# 1_P1_schdoc.net
KiCad netlist of a schematic drawn in Altium Designer
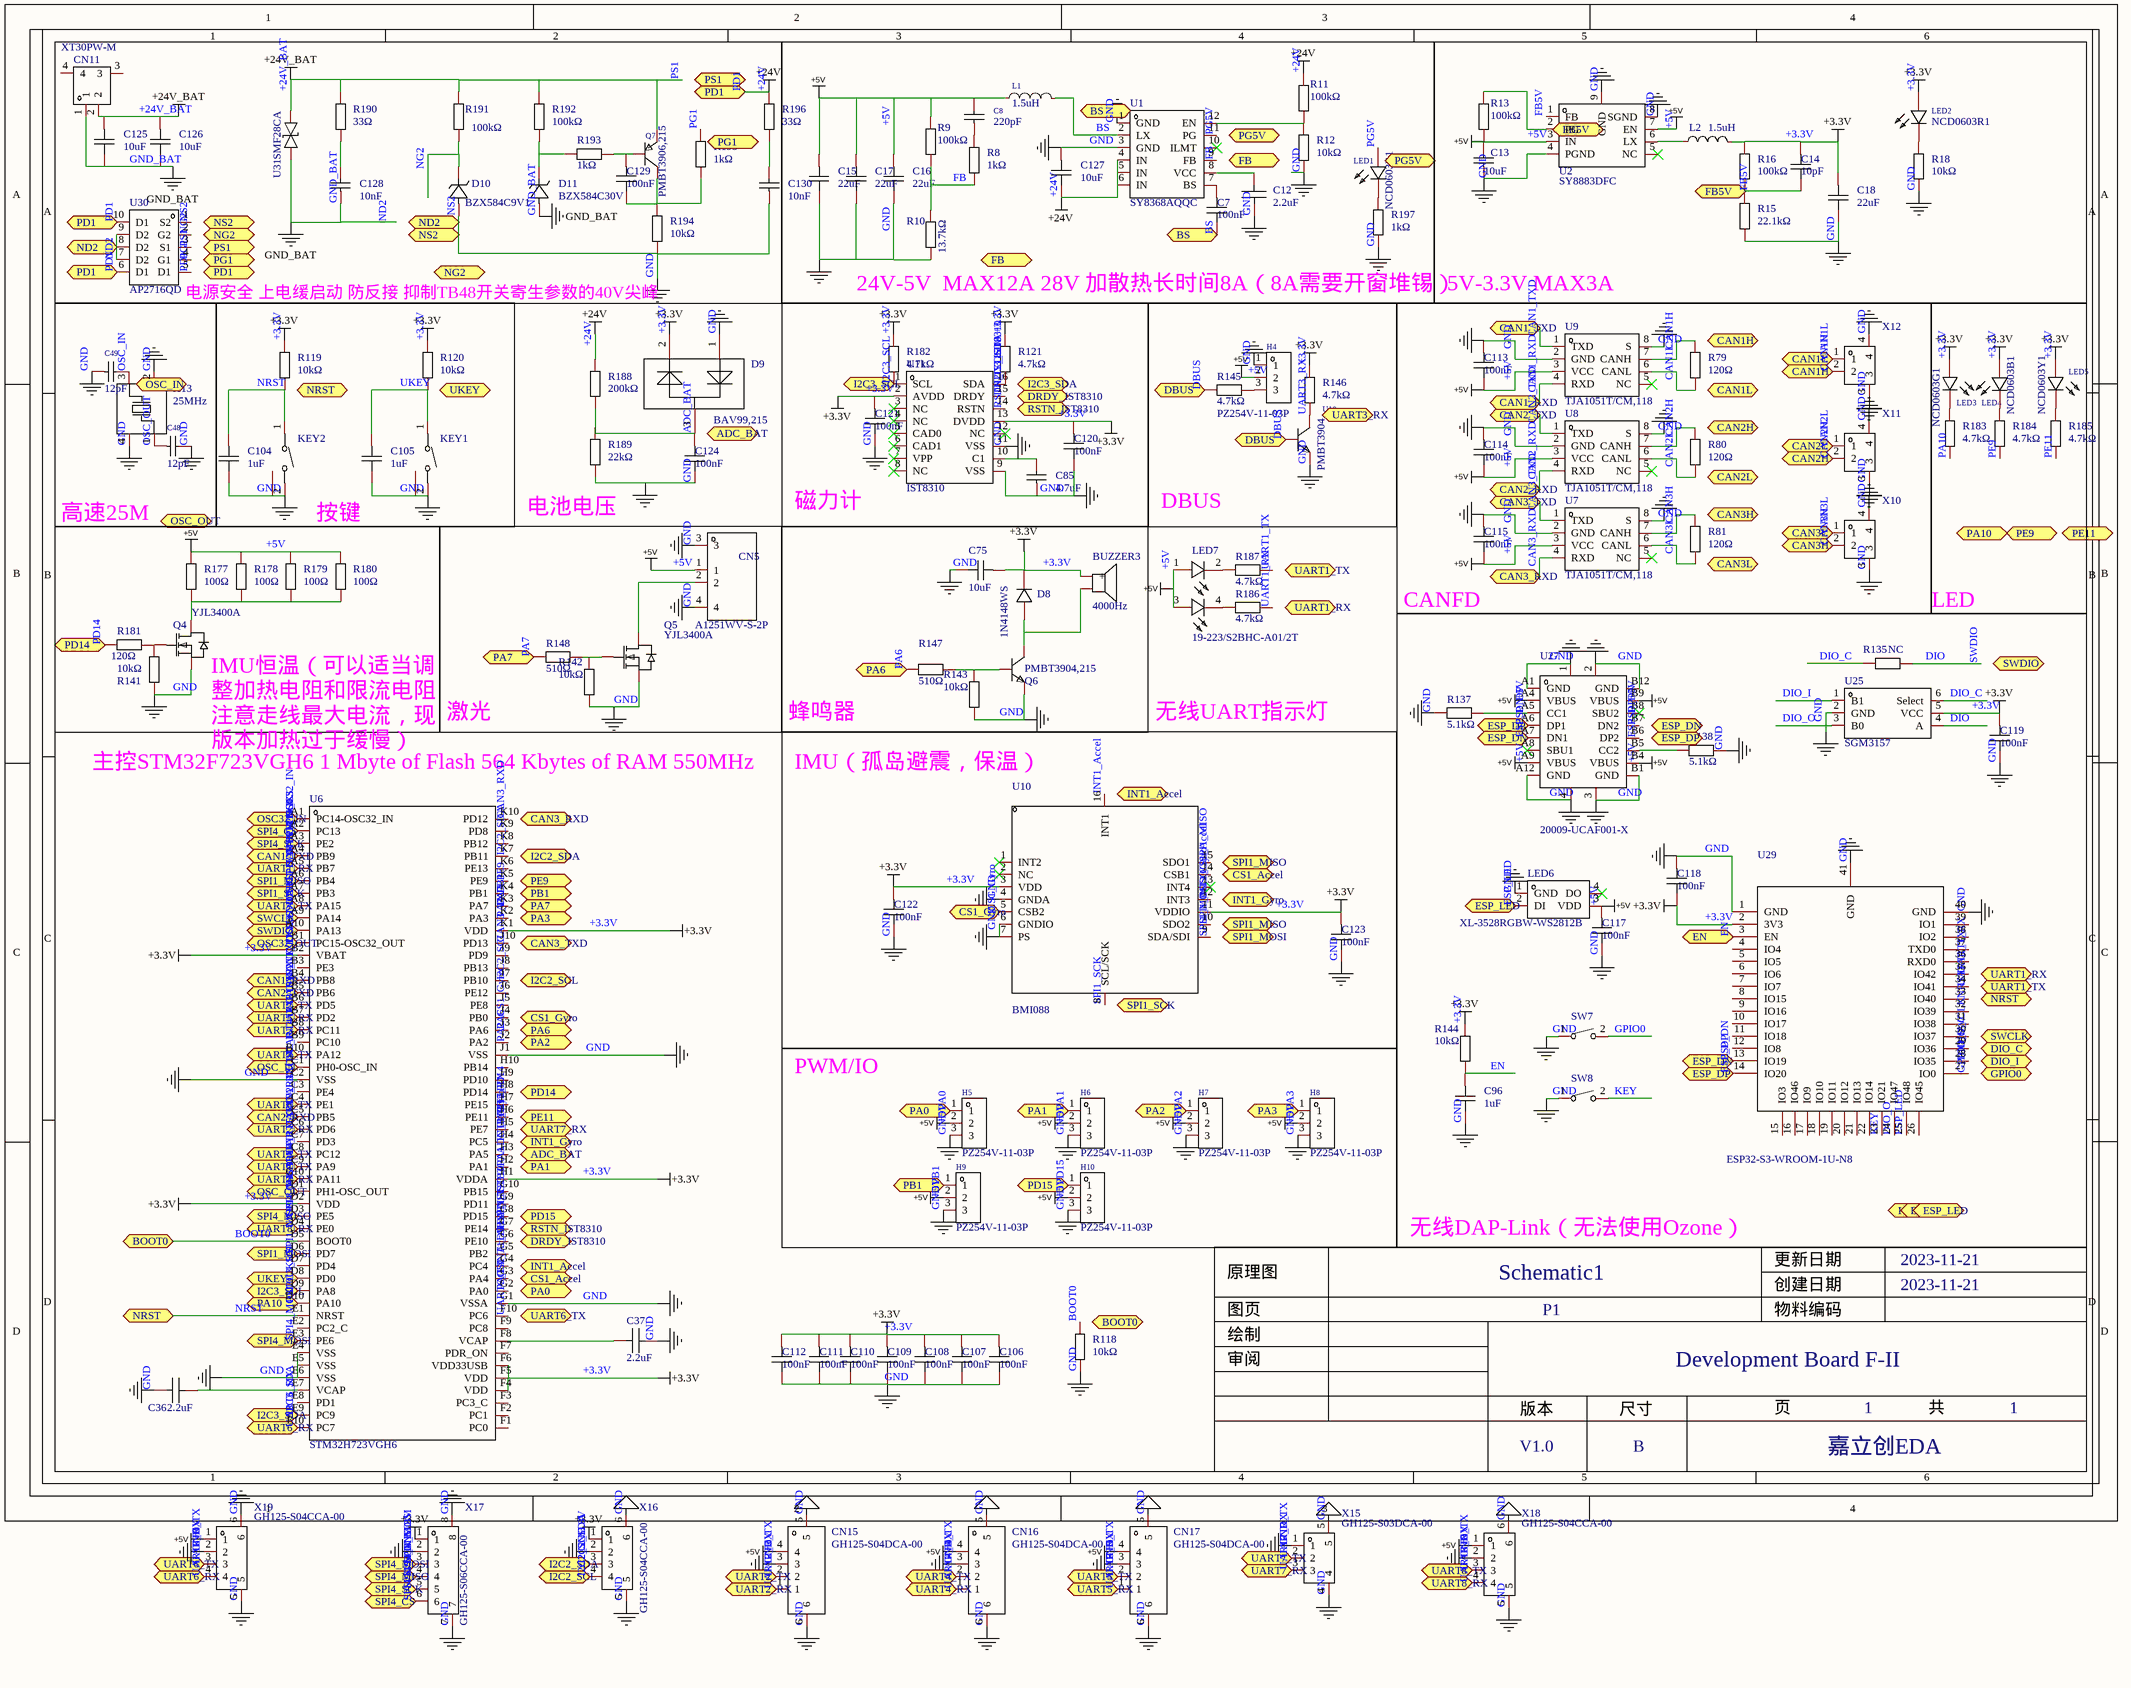
[diagram p0: 1_P1.schdoc.schdoc]

(export (version "E")
  (design (tool "Eeschema 10.0.6"))
  (components
    (comp (ref "BUZZER3")
      (value "4000Hz")
      (description "驱动方式:无源(外部驱动);构造类型:电磁式;额定电压:3V;工作电压:2V~4V;频率:4000Hz;声压(SPL):65dB@3V,10cm;长度:4mm;宽度:4mm;高度:2.5mm;")
      (fields
        (field (name "NAME") "4000Hz")
        (field (name "MANUFACTURER") "FUET(福声科技)")
        (field (name "MANUFACTURER PART") "FUET-4020")
      )
      (libsource (lib "altium-import") (part "root_0_FUET-4020_"))
    )
    (comp (ref "C7")
      (value "100nF")
      (description "容值:100nF;精度:±10%;额定电压:50V;材质(温度系数):X7R;")
      (fields
        (field (name "NAME") "100nF")
        (field (name "MANUFACTURER") "SAMSUNG(三星)")
        (field (name "MANUFACTURER PART") "CL05B104KB54PNC")
      )
      (libsource (lib "altium-import") (part "root_1_CL05B104KB54PNC_"))
    )
    (comp (ref "C8")
      (value "220pF")
      (description "容值:220pF;精度:±10%;额定电压:50V;材质(温度系数):X7R;")
      (fields
        (field (name "NAME") "220pF")
        (field (name "MANUFACTURER") "FH(风华)")
        (field (name "MANUFACTURER PART") "0402B221K500NT")
      )
      (libsource (lib "altium-import") (part "root_1_0402B221K500NT_"))
    )
    (comp (ref "C12")
      (value "2.2uF")
      (description "容值:2.2uF;精度:±20%;额定电压:6.3V;材质(温度系数):X5R;")
      (fields
        (field (name "NAME") "2.2uF")
        (field (name "MANUFACTURER") "SAMSUNG(三星)")
        (field (name "MANUFACTURER PART") "CL05A225MQ5NSNC")
      )
      (libsource (lib "altium-import") (part "root_1_CL05A225MQ5NSNC_"))
    )
    (comp (ref "C13")
      (value "10uF")
      (description "容值:10uF;精度:±20%;额定电压:6.3V;材质(温度系数):X5R;")
      (fields
        (field (name "NAME") "10uF")
        (field (name "MANUFACTURER") "SAMSUNG(三星)")
        (field (name "MANUFACTURER PART") "CL05A106MQ5NUNC")
      )
      (libsource (lib "altium-import") (part "root_1_CL05A106MQ5NUNC_"))
    )
    (comp (ref "C14")
      (value "10pF")
      (description "容值:10pF;精度:±5%;额定电压:50V;材质(温度系数):C0G;")
      (fields
        (field (name "NAME") "10pF")
        (field (name "MANUFACTURER") "SAMSUNG(三星)")
        (field (name "MANUFACTURER PART") "CL05C100JB5NNNC")
      )
      (libsource (lib "altium-import") (part "root_1_CL05C100JB5NNNC_"))
    )
    (comp (ref "C15")
      (value "22uF")
      (description "容值:22uF;精度:±20%;额定电压:6.3V;材质(温度系数):X5R;")
      (fields
        (field (name "NAME") "22uF")
        (field (name "MANUFACTURER") "SAMSUNG(三星)")
        (field (name "MANUFACTURER PART") "CL10A226MQ8NRNC")
      )
      (libsource (lib "altium-import") (part "root_1_CL10A226MQ8NRNC_"))
    )
    (comp (ref "C16")
      (value "22uF")
      (description "容值:22uF;精度:±20%;额定电压:6.3V;材质(温度系数):X5R;")
      (fields
        (field (name "NAME") "22uF")
        (field (name "MANUFACTURER") "SAMSUNG(三星)")
        (field (name "MANUFACTURER PART") "CL10A226MQ8NRNC")
      )
      (libsource (lib "altium-import") (part "root_1_CL10A226MQ8NRNC_"))
    )
    (comp (ref "C17")
      (value "22uF")
      (description "容值:22uF;精度:±20%;额定电压:6.3V;材质(温度系数):X5R;")
      (fields
        (field (name "NAME") "22uF")
        (field (name "MANUFACTURER") "SAMSUNG(三星)")
        (field (name "MANUFACTURER PART") "CL10A226MQ8NRNC")
      )
      (libsource (lib "altium-import") (part "root_1_CL10A226MQ8NRNC_"))
    )
    (comp (ref "C18")
      (value "22uF")
      (description "容值:22uF;精度:±20%;额定电压:6.3V;材质(温度系数):X5R;")
      (fields
        (field (name "NAME") "22uF")
        (field (name "MANUFACTURER") "SAMSUNG(三星)")
        (field (name "MANUFACTURER PART") "CL10A226MQ8NRNC")
      )
      (libsource (lib "altium-import") (part "root_1_CL10A226MQ8NRNC_"))
    )
    (comp (ref "C36")
      (value "2.2uF")
      (description "容值:2.2uF;精度:±20%;额定电压:6.3V;材质(温度系数):X5R;")
      (fields
        (field (name "NAME") "2.2uF")
        (field (name "MANUFACTURER") "SAMSUNG(三星)")
        (field (name "MANUFACTURER PART") "CL05A225MQ5NSNC")
      )
      (libsource (lib "altium-import") (part "root_0_CL05A225MQ5NSNC_"))
    )
    (comp (ref "C37")
      (value "2.2uF")
      (description "容值:2.2uF;精度:±20%;额定电压:6.3V;材质(温度系数):X5R;")
      (fields
        (field (name "NAME") "2.2uF")
        (field (name "MANUFACTURER") "SAMSUNG(三星)")
        (field (name "MANUFACTURER PART") "CL05A225MQ5NSNC")
      )
      (libsource (lib "altium-import") (part "root_0_CL05A225MQ5NSNC_"))
    )
    (comp (ref "C48")
      (value "12pF")
      (description "容值:12pF;精度:±5%;额定电压:50V;材质(温度系数):C0G;")
      (fields
        (field (name "NAME") "12pF")
        (field (name "MANUFACTURER") "FH(风华)")
        (field (name "MANUFACTURER PART") "0402CG120J500NT")
      )
      (libsource (lib "altium-import") (part "root_0_0402CG120J500NT_"))
    )
    (comp (ref "C49")
      (value "12pF")
      (description "容值:12pF;精度:±5%;额定电压:50V;材质(温度系数):C0G;")
      (fields
        (field (name "NAME") "12pF")
        (field (name "MANUFACTURER") "FH(风华)")
        (field (name "MANUFACTURER PART") "0402CG120J500NT")
      )
      (libsource (lib "altium-import") (part "root_0_0402CG120J500NT_"))
    )
    (comp (ref "C75")
      (value "10uF")
      (description "容值:10uF;精度:±20%;额定电压:25V;材质(温度系数):X5R;")
      (fields
        (field (name "NAME") "10uF")
        (field (name "MANUFACTURER") "SAMSUNG(三星)")
        (field (name "MANUFACTURER PART") "CL10A106MA8NRNC")
      )
      (libsource (lib "altium-import") (part "root_0_CL10A106MA8NRNC_"))
    )
    (comp (ref "C85")
      (value "4.7uF")
      (description "容值:4.7uF;精度:±20%;额定电压:10V;材质(温度系数):X5R;")
      (fields
        (field (name "NAME") "4.7uF")
        (field (name "MANUFACTURER") "SAMSUNG(三星)")
        (field (name "MANUFACTURER PART") "CL05A475MP5NRNC")
      )
      (libsource (lib "altium-import") (part "root_1_CL05A475MP5NRNC_"))
    )
    (comp (ref "C96")
      (value "1uF")
      (description "容值:1uF;精度:±10%;额定电压:25V;材质(温度系数):X5R;")
      (fields
        (field (name "NAME") "1uF")
        (field (name "MANUFACTURER") "SAMSUNG(三星)")
        (field (name "MANUFACTURER PART") "CL05A105KA5NQNC")
      )
      (libsource (lib "altium-import") (part "root_1_CL05A105KA5NQNC_"))
    )
    (comp (ref "C104")
      (value "1uF")
      (description "容值:1uF;精度:±10%;额定电压:25V;材质(温度系数):X5R;")
      (fields
        (field (name "NAME") "1uF")
        (field (name "MANUFACTURER") "SAMSUNG(三星)")
        (field (name "MANUFACTURER PART") "CL05A105KA5NQNC")
      )
      (libsource (lib "altium-import") (part "root_1_CL05A105KA5NQNC_"))
    )
    (comp (ref "C105")
      (value "1uF")
      (description "容值:1uF;精度:±10%;额定电压:25V;材质(温度系数):X5R;")
      (fields
        (field (name "NAME") "1uF")
        (field (name "MANUFACTURER") "SAMSUNG(三星)")
        (field (name "MANUFACTURER PART") "CL05A105KA5NQNC")
      )
      (libsource (lib "altium-import") (part "root_1_CL05A105KA5NQNC_"))
    )
    (comp (ref "C106")
      (value "100nF")
      (description "容值:100nF;精度:±10%;额定电压:50V;材质(温度系数):X7R;")
      (fields
        (field (name "NAME") "100nF")
        (field (name "MANUFACTURER") "SAMSUNG(三星)")
        (field (name "MANUFACTURER PART") "CL05B104KB54PNC")
      )
      (libsource (lib "altium-import") (part "root_1_CL05B104KB54PNC_"))
    )
    (comp (ref "C107")
      (value "100nF")
      (description "容值:100nF;精度:±10%;额定电压:50V;材质(温度系数):X7R;")
      (fields
        (field (name "NAME") "100nF")
        (field (name "MANUFACTURER") "SAMSUNG(三星)")
        (field (name "MANUFACTURER PART") "CL05B104KB54PNC")
      )
      (libsource (lib "altium-import") (part "root_1_CL05B104KB54PNC_"))
    )
    (comp (ref "C108")
      (value "100nF")
      (description "容值:100nF;精度:±10%;额定电压:50V;材质(温度系数):X7R;")
      (fields
        (field (name "NAME") "100nF")
        (field (name "MANUFACTURER") "SAMSUNG(三星)")
        (field (name "MANUFACTURER PART") "CL05B104KB54PNC")
      )
      (libsource (lib "altium-import") (part "root_1_CL05B104KB54PNC_"))
    )
    (comp (ref "C109")
      (value "100nF")
      (description "容值:100nF;精度:±10%;额定电压:50V;材质(温度系数):X7R;")
      (fields
        (field (name "NAME") "100nF")
        (field (name "MANUFACTURER") "SAMSUNG(三星)")
        (field (name "MANUFACTURER PART") "CL05B104KB54PNC")
      )
      (libsource (lib "altium-import") (part "root_1_CL05B104KB54PNC_"))
    )
    (comp (ref "C110")
      (value "100nF")
      (description "容值:100nF;精度:±10%;额定电压:50V;材质(温度系数):X7R;")
      (fields
        (field (name "NAME") "100nF")
        (field (name "MANUFACTURER") "SAMSUNG(三星)")
        (field (name "MANUFACTURER PART") "CL05B104KB54PNC")
      )
      (libsource (lib "altium-import") (part "root_1_CL05B104KB54PNC_"))
    )
    (comp (ref "C111")
      (value "100nF")
      (description "容值:100nF;精度:±10%;额定电压:50V;材质(温度系数):X7R;")
      (fields
        (field (name "NAME") "100nF")
        (field (name "MANUFACTURER") "SAMSUNG(三星)")
        (field (name "MANUFACTURER PART") "CL05B104KB54PNC")
      )
      (libsource (lib "altium-import") (part "root_1_CL05B104KB54PNC_"))
    )
    (comp (ref "C112")
      (value "100nF")
      (description "容值:100nF;精度:±10%;额定电压:50V;材质(温度系数):X7R;")
      (fields
        (field (name "NAME") "100nF")
        (field (name "MANUFACTURER") "SAMSUNG(三星)")
        (field (name "MANUFACTURER PART") "CL05B104KB54PNC")
      )
      (libsource (lib "altium-import") (part "root_1_CL05B104KB54PNC_"))
    )
    (comp (ref "C113")
      (value "100nF")
      (description "容值:100nF;精度:±10%;额定电压:50V;材质(温度系数):X7R;")
      (fields
        (field (name "NAME") "100nF")
        (field (name "MANUFACTURER") "SAMSUNG(三星)")
        (field (name "MANUFACTURER PART") "CL05B104KB54PNC")
      )
      (libsource (lib "altium-import") (part "root_1_CL05B104KB54PNC_"))
    )
    (comp (ref "C114")
      (value "100nF")
      (description "容值:100nF;精度:±10%;额定电压:50V;材质(温度系数):X7R;")
      (fields
        (field (name "NAME") "100nF")
        (field (name "MANUFACTURER") "SAMSUNG(三星)")
        (field (name "MANUFACTURER PART") "CL05B104KB54PNC")
      )
      (libsource (lib "altium-import") (part "root_1_CL05B104KB54PNC_"))
    )
    (comp (ref "C115")
      (value "100nF")
      (description "容值:100nF;精度:±10%;额定电压:50V;材质(温度系数):X7R;")
      (fields
        (field (name "NAME") "100nF")
        (field (name "MANUFACTURER") "SAMSUNG(三星)")
        (field (name "MANUFACTURER PART") "CL05B104KB54PNC")
      )
      (libsource (lib "altium-import") (part "root_1_CL05B104KB54PNC_"))
    )
    (comp (ref "C117")
      (value "100nF")
      (description "容值:100nF;精度:±10%;额定电压:50V;材质(温度系数):X7R;")
      (fields
        (field (name "NAME") "100nF")
        (field (name "MANUFACTURER") "SAMSUNG(三星)")
        (field (name "MANUFACTURER PART") "CL05B104KB54PNC")
      )
      (libsource (lib "altium-import") (part "root_1_CL05B104KB54PNC_"))
    )
    (comp (ref "C118")
      (value "100nF")
      (description "容值:100nF;精度:±10%;额定电压:50V;材质(温度系数):X7R;")
      (fields
        (field (name "NAME") "100nF")
        (field (name "MANUFACTURER") "SAMSUNG(三星)")
        (field (name "MANUFACTURER PART") "CL05B104KB54PNC")
      )
      (libsource (lib "altium-import") (part "root_1_CL05B104KB54PNC_"))
    )
    (comp (ref "C119")
      (value "100nF")
      (description "容值:100nF;精度:±10%;额定电压:50V;材质(温度系数):X7R;")
      (fields
        (field (name "NAME") "100nF")
        (field (name "MANUFACTURER") "SAMSUNG(三星)")
        (field (name "MANUFACTURER PART") "CL05B104KB54PNC")
      )
      (libsource (lib "altium-import") (part "root_1_CL05B104KB54PNC_"))
    )
    (comp (ref "C120")
      (value "100nF")
      (description "容值:100nF;精度:±10%;额定电压:50V;材质(温度系数):X7R;")
      (fields
        (field (name "NAME") "100nF")
        (field (name "MANUFACTURER") "SAMSUNG(三星)")
        (field (name "MANUFACTURER PART") "CL05B104KB54PNC")
      )
      (libsource (lib "altium-import") (part "root_1_CL05B104KB54PNC_"))
    )
    (comp (ref "C121")
      (value "100nF")
      (description "容值:100nF;精度:±10%;额定电压:50V;材质(温度系数):X7R;")
      (fields
        (field (name "NAME") "100nF")
        (field (name "MANUFACTURER") "SAMSUNG(三星)")
        (field (name "MANUFACTURER PART") "CL05B104KB54PNC")
      )
      (libsource (lib "altium-import") (part "root_1_CL05B104KB54PNC_"))
    )
    (comp (ref "C122")
      (value "100nF")
      (description "容值:100nF;精度:±10%;额定电压:50V;材质(温度系数):X7R;")
      (fields
        (field (name "NAME") "100nF")
        (field (name "MANUFACTURER") "SAMSUNG(三星)")
        (field (name "MANUFACTURER PART") "CL05B104KB54PNC")
      )
      (libsource (lib "altium-import") (part "root_1_CL05B104KB54PNC_"))
    )
    (comp (ref "C123")
      (value "100nF")
      (description "容值:100nF;精度:±10%;额定电压:50V;材质(温度系数):X7R;")
      (fields
        (field (name "NAME") "100nF")
        (field (name "MANUFACTURER") "SAMSUNG(三星)")
        (field (name "MANUFACTURER PART") "CL05B104KB54PNC")
      )
      (libsource (lib "altium-import") (part "root_1_CL05B104KB54PNC_"))
    )
    (comp (ref "C124")
      (value "100nF")
      (description "容值:100nF;精度:±10%;额定电压:50V;材质(温度系数):X7R;")
      (fields
        (field (name "NAME") "100nF")
        (field (name "MANUFACTURER") "SAMSUNG(三星)")
        (field (name "MANUFACTURER PART") "CL05B104KB54PNC")
      )
      (libsource (lib "altium-import") (part "root_1_CL05B104KB54PNC_"))
    )
    (comp (ref "C125")
      (value "10uF")
      (description "容值:10uF;精度:±10%;额定电压:50V;材质(温度系数):X5R;")
      (fields
        (field (name "NAME") "10uF")
        (field (name "MANUFACTURER") "muRata(村田)")
        (field (name "MANUFACTURER PART") "GRM21BR61H106KE43L")
      )
      (libsource (lib "altium-import") (part "root_1_GRM21BR61H106KE43L_"))
    )
    (comp (ref "C126")
      (value "10uF")
      (description "容值:10uF;精度:±10%;额定电压:50V;材质(温度系数):X5R;")
      (fields
        (field (name "NAME") "10uF")
        (field (name "MANUFACTURER") "muRata(村田)")
        (field (name "MANUFACTURER PART") "GRM21BR61H106KE43L")
      )
      (libsource (lib "altium-import") (part "root_1_GRM21BR61H106KE43L_"))
    )
    (comp (ref "C127")
      (value "10uF")
      (description "容值:10uF;精度:±10%;额定电压:50V;材质(温度系数):X5R;")
      (fields
        (field (name "NAME") "10uF")
        (field (name "MANUFACTURER") "muRata(村田)")
        (field (name "MANUFACTURER PART") "GRM21BR61H106KE43L")
      )
      (libsource (lib "altium-import") (part "root_1_GRM21BR61H106KE43L_"))
    )
    (comp (ref "C128")
      (value "10nF")
      (description "容值:10nF;精度:±10%;额定电压:50V;材质(温度系数):X7R;")
      (fields
        (field (name "NAME") "10nF")
        (field (name "MANUFACTURER") "SAMSUNG(三星)")
        (field (name "MANUFACTURER PART") "CL05B103KB5NNNC")
      )
      (libsource (lib "altium-import") (part "root_1_CL05B103KB5NNNC_"))
    )
    (comp (ref "C129")
      (value "100nF")
      (description "容值:100nF;精度:±10%;额定电压:50V;材质(温度系数):X7R;")
      (fields
        (field (name "NAME") "100nF")
        (field (name "MANUFACTURER") "SAMSUNG(三星)")
        (field (name "MANUFACTURER PART") "CL05B104KB54PNC")
      )
      (libsource (lib "altium-import") (part "root_1_CL05B104KB54PNC_"))
    )
    (comp (ref "C130")
      (value "10nF")
      (description "容值:10nF;精度:±10%;额定电压:50V;材质(温度系数):X7R;")
      (fields
        (field (name "NAME") "10nF")
        (field (name "MANUFACTURER") "SAMSUNG(三星)")
        (field (name "MANUFACTURER PART") "CL05B103KB5NNNC")
      )
      (libsource (lib "altium-import") (part "root_1_CL05B103KB5NNNC_"))
    )
    (comp (ref "CN5")
      (value "A1251WV-S-2P")
      (description "参考系列:-;间距:1.25mm;插针结构:1x2P;排数:1;每排PIN数:2;行距:-;安装方式:-;触头材质:磷青铜;")
      (fields (field (name "NAME") "A1251WV-S-2P") (field (name "MANUFACTURER") "CJT(长江连接器)"))
      (libsource (lib "altium-import") (part "root_0_A1251WV-S-2P_"))
    )
    (comp (ref "CN11")
      (value "XT30PW-M")
      (description "Socket,DCsupply,XT30,male,PIN:2")
      (fields (field (name "NAME") "XT30PW-M") (field (name "MANUFACTURER") "AMASS(艾迈斯)"))
      (libsource (lib "altium-import") (part "root_1_XT30PW-M_"))
    )
    (comp (ref "CN15")
      (value "GH125-S04DCA-00")
      (description "参考系列:-;间距:1.25mm;插针结构:1x4P;排数:1;每排PIN数:4;行距:-;公母:公型插针;安装方式:卧贴;额定电流:1A;工作温度范围:-25℃~+85℃;")
      (fields (field (name "NAME") "GH125-S04DCA-00") (field (name "MANUFACTURER") "JS(钜硕电子)"))
      (libsource (lib "altium-import") (part "root_1_GH125-S04DCA-00_"))
    )
    (comp (ref "CN16")
      (value "GH125-S04DCA-00")
      (description "参考系列:-;间距:1.25mm;插针结构:1x4P;排数:1;每排PIN数:4;行距:-;公母:公型插针;安装方式:卧贴;额定电流:1A;工作温度范围:-25℃~+85℃;")
      (fields (field (name "NAME") "GH125-S04DCA-00") (field (name "MANUFACTURER") "JS(钜硕电子)"))
      (libsource (lib "altium-import") (part "root_1_GH125-S04DCA-00_"))
    )
    (comp (ref "CN17")
      (value "GH125-S04DCA-00")
      (description "参考系列:-;间距:1.25mm;插针结构:1x4P;排数:1;每排PIN数:4;行距:-;公母:公型插针;安装方式:卧贴;额定电流:1A;工作温度范围:-25℃~+85℃;")
      (fields (field (name "NAME") "GH125-S04DCA-00") (field (name "MANUFACTURER") "JS(钜硕电子)"))
      (libsource (lib "altium-import") (part "root_1_GH125-S04DCA-00_"))
    )
    (comp (ref "D8")
      (value "1N4148WS")
      (fields (field (name "NAME") "1N4148WS") (field (name "MANUFACTURER") "CJ(江苏长电/长晶)"))
      (libsource (lib "altium-import") (part "root_3_1N4148WS_C2128_"))
    )
    (comp (ref "D9")
      (value "BAV99,215")
      (description "二极管配置:1对串联式;功率:250mW;直流反向耐压(Vr):100V;平均整流电流(Io):215mA;正向压降(Vf):1.25V@150mA;反向恢复时间(trr):4ns;")
      (fields (field (name "NAME") "BAV99,215") (field (name "MANUFACTURER") "Nexperia(安世)"))
      (libsource (lib "altium-import") (part "root_2_BAV99,215_"))
    )
    (comp (ref "D10")
      (value "BZX584C9V1")
      (description "二极管配置:独立式;稳压值(标称值):9.1V;稳压值(范围):8.5V~9.6V;精度:-;功率:200mW;反向电流(Ir):200nA@7V;阻抗(Zzt):15Ω;")
      (fields (field (name "NAME") "BZX584C9V1") (field (name "MANUFACTURER") "YANGJIE(扬杰)"))
      (libsource (lib "altium-import") (part "root_3_BZX584C9V1_"))
    )
    (comp (ref "D11")
      (value "BZX584C30V")
      (description "二极管配置:独立式;稳压值(标称值):30V;稳压值(范围):28V~32V;精度:-;功率:200mW;反向电流(Ir):50nA@21V;阻抗(Zzt):80Ω;")
      (fields (field (name "NAME") "BZX584C30V") (field (name "MANUFACTURER") "YANGJIE(扬杰)"))
      (libsource (lib "altium-import") (part "root_3_BZX584C30V_"))
    )
    (comp (ref "H4")
      (value "PZ254V-11-03P")
      (fields (field (name "NAME") "PZ254V-11-03P") (field (name "MANUFACTURER") "XFCN(兴飞)"))
      (libsource (lib "altium-import") (part "root_0_PZ254V-11-03P_"))
    )
    (comp (ref "H5")
      (value "PZ254V-11-03P")
      (fields (field (name "NAME") "PZ254V-11-03P") (field (name "MANUFACTURER") "XFCN(兴飞)"))
      (libsource (lib "altium-import") (part "root_0_PZ254V-11-03P_"))
    )
    (comp (ref "H6")
      (value "PZ254V-11-03P")
      (fields (field (name "NAME") "PZ254V-11-03P") (field (name "MANUFACTURER") "XFCN(兴飞)"))
      (libsource (lib "altium-import") (part "root_0_PZ254V-11-03P_"))
    )
    (comp (ref "H7")
      (value "PZ254V-11-03P")
      (fields (field (name "NAME") "PZ254V-11-03P") (field (name "MANUFACTURER") "XFCN(兴飞)"))
      (libsource (lib "altium-import") (part "root_0_PZ254V-11-03P_"))
    )
    (comp (ref "H8")
      (value "PZ254V-11-03P")
      (fields (field (name "NAME") "PZ254V-11-03P") (field (name "MANUFACTURER") "XFCN(兴飞)"))
      (libsource (lib "altium-import") (part "root_0_PZ254V-11-03P_"))
    )
    (comp (ref "H9")
      (value "PZ254V-11-03P")
      (fields (field (name "NAME") "PZ254V-11-03P") (field (name "MANUFACTURER") "XFCN(兴飞)"))
      (libsource (lib "altium-import") (part "root_0_PZ254V-11-03P_"))
    )
    (comp (ref "H10")
      (value "PZ254V-11-03P")
      (fields (field (name "NAME") "PZ254V-11-03P") (field (name "MANUFACTURER") "XFCN(兴飞)"))
      (libsource (lib "altium-import") (part "root_0_PZ254V-11-03P_"))
    )
    (comp (ref "KEY1")
      (value "1TS003B-2500-3500A-CT")
      (fields (field (name "MANUFACTURER") "HYP(鸿源精密)"))
      (libsource (lib "altium-import") (part "root_3_1TS003B-2500-3500A-CT_"))
    )
    (comp (ref "KEY2")
      (value "1TS003B-2500-3500A-CT")
      (fields (field (name "MANUFACTURER") "HYP(鸿源精密)"))
      (libsource (lib "altium-import") (part "root_3_1TS003B-2500-3500A-CT_"))
    )
    (comp (ref "L1")
      (value "1.5uH")
      (description "类型:一体成型电感;电感值:1.5uH;精度:±20%;额定电流:9A;饱和电流(Isat):15A;")
      (fields
        (field (name "NAME") "1.5uH")
        (field (name "MANUFACTURER") "cjiang(长江微电)")
        (field (name "MANUFACTURER PART") "FXL0624-1R5-M")
      )
      (libsource (lib "altium-import") (part "root_0_FXL0624-1R5-M_"))
    )
    (comp (ref "L2")
      (value "1.5uH")
      (description "电感值:1.5uH;精度:±20%;额定电流:-;饱和电流(Isat):-;")
      (fields
        (field (name "NAME") "1.5uH")
        (field (name "MANUFACTURER") "muRata(村田)")
        (field (name "MANUFACTURER PART") "DFE201610E-1R5M=P2")
      )
      (libsource (lib "altium-import") (part "root_0_DFE201610E-1R5M=P2_"))
    )
    (comp (ref "LED1")
      (value "NCD0603R1")
      (description "发光颜色:红灯;")
      (fields (field (name "NAME") "NCD0603R1") (field (name "MANUFACTURER") "国星光电"))
      (libsource (lib "altium-import") (part "root_1_NCD0603R1_C84263_"))
    )
    (comp (ref "LED2")
      (value "NCD0603R1")
      (description "发光颜色:红灯;")
      (fields (field (name "NAME") "NCD0603R1") (field (name "MANUFACTURER") "国星光电"))
      (libsource (lib "altium-import") (part "root_1_NCD0603R1_C84263_"))
    )
    (comp (ref "LED3")
      (value "NCD0603G1")
      (description "发光颜色:翠绿;")
      (fields (field (name "NAME") "NCD0603G1") (field (name "MANUFACTURER") "国星光电"))
      (libsource (lib "altium-import") (part "root_3_NCD0603G1_"))
    )
    (comp (ref "LED4")
      (value "NCD0603B1")
      (description "发光颜色:蓝灯;")
      (fields (field (name "NAME") "NCD0603B1") (field (name "MANUFACTURER") "国星光电"))
      (libsource (lib "altium-import") (part "root_1_NCD0603B1_"))
    )
    (comp (ref "LED5")
      (value "NCD0603Y1")
      (description "发光颜色:黄灯;")
      (fields (field (name "NAME") "NCD0603Y1") (field (name "MANUFACTURER") "国星光电"))
      (libsource (lib "altium-import") (part "root_3_NCD0603Y1_"))
    )
    (comp (ref "LED6")
      (value "XL-3528RGBW-WS2812B")
      (description "发光颜色:RGB三色;二极管配置:-;主波长:618nm~623nm；520nm~525nm；467nm~472nm;功率:50mW；50mW；45mW;安装方式:正贴;")
      (fields (field (name "NAME") "XL-3528RGBW-WS2812B") (field (name "MANUFACTURER") "XINGLIGHT(成兴光)"))
      (libsource (lib "altium-import") (part "root_0_XL-3528RGBW-WS2812B_"))
    )
    (comp (ref "LED7")
      (value "19-223/S2BHC-A01/2T")
      (description "发光颜色:橙灯,蓝灯;二极管配置:-;透镜颜色:无色透明;主波长:470nm；605nm;色温:-;功率:60mW；75mW;发光角度:120°;安装方式:-;工作温度:-40℃~+85℃;")
      (fields (field (name "NAME") "19-223/S2BHC-A01/2T") (field (name "MANUFACTURER") "EVERLIGHT(亿光)"))
      (libsource (lib "altium-import") (part "root_2_19-223/S2BHC-A01/2T_"))
    )
    (comp (ref "Q4")
      (value "YJL3400A")
      (description "类型:N沟道;漏源电压(Vdss):30V;连续漏极电流(Id):5.6A;功率(Pd):1.2W;导通电阻(RDS(on)@Vgs,Id):27mΩ@10V,5.6A;")
      (fields (field (name "NAME") "YJL3400A") (field (name "MANUFACTURER") "YANGJIE(扬杰)"))
      (libsource (lib "altium-import") (part "root_0_YJL3400A_"))
    )
    (comp (ref "Q5")
      (value "YJL3400A")
      (description "类型:N沟道;漏源电压(Vdss):30V;连续漏极电流(Id):5.6A;功率(Pd):1.2W;导通电阻(RDS(on)@Vgs,Id):27mΩ@10V,5.6A;")
      (fields (field (name "NAME") "YJL3400A") (field (name "MANUFACTURER") "YANGJIE(扬杰)"))
      (libsource (lib "altium-import") (part "root_0_YJL3400A_"))
    )
    (comp (ref "Q6")
      (value "PMBT3904,215")
      (description "晶体管类型:NPN;集射极击穿电压(Vceo):40V;集电极电流(Ic):200mA;功率(Pd):250mW;直流电流增益(hFE@Ic,Vce):100@10mA,1V;")
      (fields (field (name "NAME") "PMBT3904,215") (field (name "MANUFACTURER") "Nexperia(安世)"))
      (libsource (lib "altium-import") (part "root_0_PMBT3904,215_"))
    )
    (comp (ref "Q7")
      (value "PMBT3906,215")
      (description "晶体管类型:PNP;集射极击穿电压(Vceo):40V;集电极电流(Ic):200mA;功率(Pd):250mW;直流电流增益(hFE@Ic,Vce):100@10mA,1V;")
      (fields (field (name "NAME") "PMBT3906,215") (field (name "MANUFACTURER") "Nexperia(安世)"))
      (libsource (lib "altium-import") (part "root_2_mirrored_PMBT3906,215_"))
    )
    (comp (ref "R8")
      (value "1kΩ")
      (description "电阻类型:厚膜电阻;阻值:1kΩ;精度:±1%;功率:62.5mW;")
      (fields
        (field (name "NAME") "1kΩ")
        (field (name "MANUFACTURER") "UNI-ROYAL(厚声)")
        (field (name "MANUFACTURER PART") "0402WGF1001TCE")
      )
      (libsource (lib "altium-import") (part "root_1_0402WGF1001TCE_"))
    )
    (comp (ref "R9")
      (value "100kΩ")
      (description "电阻类型:厚膜电阻;阻值:100kΩ;精度:±1%;功率:62.5mW;")
      (fields
        (field (name "NAME") "100kΩ")
        (field (name "MANUFACTURER") "UNI-ROYAL(厚声)")
        (field (name "MANUFACTURER PART") "0402WGF1003TCE")
      )
      (libsource (lib "altium-import") (part "root_1_0402WGF1003TCE_"))
    )
    (comp (ref "R10")
      (value "13.7kΩ")
      (description "电阻类型:厚膜电阻;阻值:13.7kΩ;精度:±1%;功率:62.5mW;温度系数:±100ppm/℃;")
      (fields
        (field (name "NAME") "13.7kΩ")
        (field (name "MANUFACTURER") "UNI-ROYAL(厚声)")
        (field (name "MANUFACTURER PART") "0402WGF1372TCE")
      )
      (libsource (lib "altium-import") (part "root_1_0402WGF1372TCE_"))
    )
    (comp (ref "R11")
      (value "100kΩ")
      (description "电阻类型:厚膜电阻;阻值:100kΩ;精度:±1%;功率:62.5mW;")
      (fields
        (field (name "NAME") "100kΩ")
        (field (name "MANUFACTURER") "UNI-ROYAL(厚声)")
        (field (name "MANUFACTURER PART") "0402WGF1003TCE")
      )
      (libsource (lib "altium-import") (part "root_1_0402WGF1003TCE_"))
    )
    (comp (ref "R12")
      (value "10kΩ")
      (description "电阻类型:厚膜电阻;阻值:10kΩ;精度:±1%;功率:62.5mW;温度系数:±100ppm/℃;")
      (fields
        (field (name "NAME") "10kΩ")
        (field (name "MANUFACTURER") "UNI-ROYAL(厚声)")
        (field (name "MANUFACTURER PART") "0402WGF1002TCE")
      )
      (libsource (lib "altium-import") (part "root_1_0402WGF1002TCE_"))
    )
    (comp (ref "R13")
      (value "100kΩ")
      (description "电阻类型:厚膜电阻;阻值:100kΩ;精度:±1%;功率:62.5mW;")
      (fields
        (field (name "NAME") "100kΩ")
        (field (name "MANUFACTURER") "UNI-ROYAL(厚声)")
        (field (name "MANUFACTURER PART") "0402WGF1003TCE")
      )
      (libsource (lib "altium-import") (part "root_1_0402WGF1003TCE_"))
    )
    (comp (ref "R15")
      (value "22.1kΩ")
      (description "电阻类型:厚膜电阻;阻值:22.1kΩ;精度:±1%;功率:62.5mW;")
      (fields
        (field (name "NAME") "22.1kΩ")
        (field (name "MANUFACTURER") "UNI-ROYAL(厚声)")
        (field (name "MANUFACTURER PART") "0402WGF2212TCE")
      )
      (libsource (lib "altium-import") (part "root_1_0402WGF2212TCE_"))
    )
    (comp (ref "R16")
      (value "100kΩ")
      (description "电阻类型:厚膜电阻;阻值:100kΩ;精度:±1%;功率:62.5mW;")
      (fields
        (field (name "NAME") "100kΩ")
        (field (name "MANUFACTURER") "UNI-ROYAL(厚声)")
        (field (name "MANUFACTURER PART") "0402WGF1003TCE")
      )
      (libsource (lib "altium-import") (part "root_3_0402WGF1003TCE_"))
    )
    (comp (ref "R18")
      (value "10kΩ")
      (description "电阻类型:厚膜电阻;阻值:10kΩ;精度:±1%;功率:62.5mW;温度系数:±100ppm/℃;")
      (fields
        (field (name "NAME") "10kΩ")
        (field (name "MANUFACTURER") "UNI-ROYAL(厚声)")
        (field (name "MANUFACTURER PART") "0402WGF1002TCE")
      )
      (libsource (lib "altium-import") (part "root_1_0402WGF1002TCE_"))
    )
    (comp (ref "R79")
      (value "120Ω")
      (description "电阻类型:厚膜电阻;阻值:120Ω;精度:±1%;功率:62.5mW;")
      (fields
        (field (name "NAME") "120Ω")
        (field (name "MANUFACTURER") "UNI-ROYAL(厚声)")
        (field (name "MANUFACTURER PART") "0402WGF1200TCE")
      )
      (libsource (lib "altium-import") (part "root_1_0402WGF1200TCE_"))
    )
    (comp (ref "R80")
      (value "120Ω")
      (description "电阻类型:厚膜电阻;阻值:120Ω;精度:±1%;功率:62.5mW;")
      (fields
        (field (name "NAME") "120Ω")
        (field (name "MANUFACTURER") "UNI-ROYAL(厚声)")
        (field (name "MANUFACTURER PART") "0402WGF1200TCE")
      )
      (libsource (lib "altium-import") (part "root_1_0402WGF1200TCE_"))
    )
    (comp (ref "R81")
      (value "120Ω")
      (description "电阻类型:厚膜电阻;阻值:120Ω;精度:±1%;功率:62.5mW;")
      (fields
        (field (name "NAME") "120Ω")
        (field (name "MANUFACTURER") "UNI-ROYAL(厚声)")
        (field (name "MANUFACTURER PART") "0402WGF1200TCE")
      )
      (libsource (lib "altium-import") (part "root_1_0402WGF1200TCE_"))
    )
    (comp (ref "R118")
      (value "10kΩ")
      (description "电阻类型:厚膜电阻;阻值:10kΩ;精度:±1%;功率:62.5mW;温度系数:±100ppm/℃;")
      (fields
        (field (name "NAME") "10kΩ")
        (field (name "MANUFACTURER") "UNI-ROYAL(厚声)")
        (field (name "MANUFACTURER PART") "0402WGF1002TCE")
      )
      (libsource (lib "altium-import") (part "root_1_0402WGF1002TCE_"))
    )
    (comp (ref "R119")
      (value "10kΩ")
      (description "电阻类型:厚膜电阻;阻值:10kΩ;精度:±1%;功率:62.5mW;温度系数:±100ppm/℃;")
      (fields
        (field (name "NAME") "10kΩ")
        (field (name "MANUFACTURER") "UNI-ROYAL(厚声)")
        (field (name "MANUFACTURER PART") "0402WGF1002TCE")
      )
      (libsource (lib "altium-import") (part "root_1_0402WGF1002TCE_"))
    )
    (comp (ref "R120")
      (value "10kΩ")
      (description "电阻类型:厚膜电阻;阻值:10kΩ;精度:±1%;功率:62.5mW;温度系数:±100ppm/℃;")
      (fields
        (field (name "NAME") "10kΩ")
        (field (name "MANUFACTURER") "UNI-ROYAL(厚声)")
        (field (name "MANUFACTURER PART") "0402WGF1002TCE")
      )
      (libsource (lib "altium-import") (part "root_1_0402WGF1002TCE_"))
    )
    (comp (ref "R121")
      (value "4.7kΩ")
      (description "电阻类型:厚膜电阻;阻值:4.7kΩ;精度:±1%;功率:62.5mW;")
      (fields
        (field (name "NAME") "4.7kΩ")
        (field (name "MANUFACTURER") "UNI-ROYAL(厚声)")
        (field (name "MANUFACTURER PART") "0402WGF4701TCE")
      )
      (libsource (lib "altium-import") (part "root_1_0402WGF4701TCE_"))
    )
    (comp (ref "R135")
      (value "NC")
      (fields (field (name "Comment") "R0402"))
      (libsource (lib "altium-import") (part "root_0_R0402_"))
    )
    (comp (ref "R137")
      (value "5.1kΩ")
      (description "电阻类型:厚膜电阻;阻值:5.1kΩ;精度:±1%;功率:62.5mW;")
      (fields
        (field (name "NAME") "5.1kΩ")
        (field (name "MANUFACTURER") "UNI-ROYAL(厚声)")
        (field (name "MANUFACTURER PART") "0402WGF5101TCE")
      )
      (libsource (lib "altium-import") (part "root_0_0402WGF5101TCE_"))
    )
    (comp (ref "R138")
      (value "5.1kΩ")
      (description "电阻类型:厚膜电阻;阻值:5.1kΩ;精度:±1%;功率:62.5mW;")
      (fields
        (field (name "NAME") "5.1kΩ")
        (field (name "MANUFACTURER") "UNI-ROYAL(厚声)")
        (field (name "MANUFACTURER PART") "0402WGF5101TCE")
      )
      (libsource (lib "altium-import") (part "root_0_0402WGF5101TCE_"))
    )
    (comp (ref "R141")
      (value "10kΩ")
      (description "电阻类型:厚膜电阻;阻值:10kΩ;精度:±1%;功率:62.5mW;")
      (fields
        (field (name "NAME") "10kΩ")
        (field (name "MANUFACTURER") "UNI-ROYAL(厚声)")
        (field (name "MANUFACTURER PART") "0402WGF1002TCE")
      )
      (libsource (lib "altium-import") (part "root_1_0402WGF1002TCE_"))
    )
    (comp (ref "R142")
      (value "10kΩ")
      (description "电阻类型:厚膜电阻;阻值:10kΩ;精度:±1%;功率:62.5mW;")
      (fields
        (field (name "NAME") "10kΩ")
        (field (name "MANUFACTURER") "UNI-ROYAL(厚声)")
        (field (name "MANUFACTURER PART") "0402WGF1002TCE")
      )
      (libsource (lib "altium-import") (part "root_1_0402WGF1002TCE_"))
    )
    (comp (ref "R143")
      (value "10kΩ")
      (description "电阻类型:厚膜电阻;阻值:10kΩ;精度:±1%;功率:62.5mW;")
      (fields
        (field (name "NAME") "10kΩ")
        (field (name "MANUFACTURER") "UNI-ROYAL(厚声)")
        (field (name "MANUFACTURER PART") "0402WGF1002TCE")
      )
      (libsource (lib "altium-import") (part "root_1_0402WGF1002TCE_"))
    )
    (comp (ref "R144")
      (value "10kΩ")
      (description "电阻类型:厚膜电阻;阻值:10kΩ;精度:±1%;功率:62.5mW;")
      (fields
        (field (name "NAME") "10kΩ")
        (field (name "MANUFACTURER") "UNI-ROYAL(厚声)")
        (field (name "MANUFACTURER PART") "0402WGF1002TCE")
      )
      (libsource (lib "altium-import") (part "root_1_0402WGF1002TCE_"))
    )
    (comp (ref "R145")
      (value "4.7kΩ")
      (description "电阻类型:厚膜电阻;阻值:4.7kΩ;精度:±1%;功率:62.5mW;")
      (fields
        (field (name "NAME") "4.7kΩ")
        (field (name "MANUFACTURER") "UNI-ROYAL(厚声)")
        (field (name "MANUFACTURER PART") "0402WGF4701TCE")
      )
      (libsource (lib "altium-import") (part "root_0_0402WGF4701TCE_"))
    )
    (comp (ref "R146")
      (value "4.7kΩ")
      (description "电阻类型:厚膜电阻;阻值:4.7kΩ;精度:±1%;功率:62.5mW;")
      (fields
        (field (name "NAME") "4.7kΩ")
        (field (name "MANUFACTURER") "UNI-ROYAL(厚声)")
        (field (name "MANUFACTURER PART") "0402WGF4701TCE")
      )
      (libsource (lib "altium-import") (part "root_1_0402WGF4701TCE_"))
    )
    (comp (ref "R147")
      (value "510Ω")
      (description "电阻类型:厚膜电阻;阻值:510Ω;精度:±1%;功率:62.5mW;")
      (fields
        (field (name "NAME") "510Ω")
        (field (name "MANUFACTURER") "UNI-ROYAL(厚声)")
        (field (name "MANUFACTURER PART") "0402WGF5100TCE")
      )
      (libsource (lib "altium-import") (part "root_0_0402WGF5100TCE_"))
    )
    (comp (ref "R148")
      (value "510Ω")
      (description "电阻类型:厚膜电阻;阻值:510Ω;精度:±1%;功率:62.5mW;")
      (fields
        (field (name "NAME") "510Ω")
        (field (name "MANUFACTURER") "UNI-ROYAL(厚声)")
        (field (name "MANUFACTURER PART") "0402WGF5100TCE")
      )
      (libsource (lib "altium-import") (part "root_0_0402WGF5100TCE_"))
    )
    (comp (ref "R177")
      (value "100Ω")
      (description "电阻类型:厚膜电阻;阻值:100Ω;精度:±1%;功率:100mW;温度系数:±200ppm/℃;")
      (fields
        (field (name "NAME") "100Ω")
        (field (name "MANUFACTURER") "UNI-ROYAL(厚声)")
        (field (name "MANUFACTURER PART") "0603WAF1000T5E")
      )
      (libsource (lib "altium-import") (part "root_1_0603WAF1000T5E_"))
    )
    (comp (ref "R178")
      (value "100Ω")
      (description "电阻类型:厚膜电阻;阻值:100Ω;精度:±1%;功率:100mW;温度系数:±200ppm/℃;")
      (fields
        (field (name "NAME") "100Ω")
        (field (name "MANUFACTURER") "UNI-ROYAL(厚声)")
        (field (name "MANUFACTURER PART") "0603WAF1000T5E")
      )
      (libsource (lib "altium-import") (part "root_1_0603WAF1000T5E_"))
    )
    (comp (ref "R179")
      (value "100Ω")
      (description "电阻类型:厚膜电阻;阻值:100Ω;精度:±1%;功率:100mW;温度系数:±200ppm/℃;")
      (fields
        (field (name "NAME") "100Ω")
        (field (name "MANUFACTURER") "UNI-ROYAL(厚声)")
        (field (name "MANUFACTURER PART") "0603WAF1000T5E")
      )
      (libsource (lib "altium-import") (part "root_1_0603WAF1000T5E_"))
    )
    (comp (ref "R180")
      (value "100Ω")
      (description "电阻类型:厚膜电阻;阻值:100Ω;精度:±1%;功率:100mW;温度系数:±200ppm/℃;")
      (fields
        (field (name "NAME") "100Ω")
        (field (name "MANUFACTURER") "UNI-ROYAL(厚声)")
        (field (name "MANUFACTURER PART") "0603WAF1000T5E")
      )
      (libsource (lib "altium-import") (part "root_1_0603WAF1000T5E_"))
    )
    (comp (ref "R181")
      (value "120Ω")
      (description "电阻类型:厚膜电阻;阻值:120Ω;精度:±1%;功率:62.5mW;")
      (fields
        (field (name "NAME") "120Ω")
        (field (name "MANUFACTURER") "UNI-ROYAL(厚声)")
        (field (name "MANUFACTURER PART") "0402WGF1200TCE")
      )
      (libsource (lib "altium-import") (part "root_2_0402WGF1200TCE_"))
    )
    (comp (ref "R182")
      (value "4.7kΩ")
      (description "电阻类型:厚膜电阻;阻值:4.7kΩ;精度:±1%;功率:62.5mW;")
      (fields
        (field (name "NAME") "4.7kΩ")
        (field (name "MANUFACTURER") "UNI-ROYAL(厚声)")
        (field (name "MANUFACTURER PART") "0402WGF4701TCE")
      )
      (libsource (lib "altium-import") (part "root_1_0402WGF4701TCE_"))
    )
    (comp (ref "R183")
      (value "4.7kΩ")
      (description "电阻类型:厚膜电阻;阻值:4.7kΩ;精度:±1%;功率:62.5mW;")
      (fields
        (field (name "NAME") "4.7kΩ")
        (field (name "MANUFACTURER") "UNI-ROYAL(厚声)")
        (field (name "MANUFACTURER PART") "0402WGF4701TCE")
      )
      (libsource (lib "altium-import") (part "root_1_0402WGF4701TCE_"))
    )
    (comp (ref "R184")
      (value "4.7kΩ")
      (description "电阻类型:厚膜电阻;阻值:4.7kΩ;精度:±1%;功率:62.5mW;")
      (fields
        (field (name "NAME") "4.7kΩ")
        (field (name "MANUFACTURER") "UNI-ROYAL(厚声)")
        (field (name "MANUFACTURER PART") "0402WGF4701TCE")
      )
      (libsource (lib "altium-import") (part "root_1_0402WGF4701TCE_"))
    )
    (comp (ref "R185")
      (value "4.7kΩ")
      (description "电阻类型:厚膜电阻;阻值:4.7kΩ;精度:±1%;功率:62.5mW;")
      (fields
        (field (name "NAME") "4.7kΩ")
        (field (name "MANUFACTURER") "UNI-ROYAL(厚声)")
        (field (name "MANUFACTURER PART") "0402WGF4701TCE")
      )
      (libsource (lib "altium-import") (part "root_1_0402WGF4701TCE_"))
    )
    (comp (ref "R186")
      (value "4.7kΩ")
      (description "电阻类型:厚膜电阻;阻值:4.7kΩ;精度:±1%;功率:62.5mW;")
      (fields
        (field (name "NAME") "4.7kΩ")
        (field (name "MANUFACTURER") "UNI-ROYAL(厚声)")
        (field (name "MANUFACTURER PART") "0402WGF4701TCE")
      )
      (libsource (lib "altium-import") (part "root_0_0402WGF4701TCE_"))
    )
    (comp (ref "R187")
      (value "4.7kΩ")
      (description "电阻类型:厚膜电阻;阻值:4.7kΩ;精度:±1%;功率:62.5mW;")
      (fields
        (field (name "NAME") "4.7kΩ")
        (field (name "MANUFACTURER") "UNI-ROYAL(厚声)")
        (field (name "MANUFACTURER PART") "0402WGF4701TCE")
      )
      (libsource (lib "altium-import") (part "root_0_0402WGF4701TCE_"))
    )
    (comp (ref "R188")
      (value "200kΩ")
      (description "电阻类型:厚膜电阻;阻值:200kΩ;精度:±1%;功率:62.5mW;温度系数:±100ppm/℃;")
      (fields
        (field (name "NAME") "200kΩ")
        (field (name "MANUFACTURER") "UNI-ROYAL(厚声)")
        (field (name "MANUFACTURER PART") "0402WGF2003TCE")
      )
      (libsource (lib "altium-import") (part "root_1_0402WGF2003TCE_"))
    )
    (comp (ref "R189")
      (value "22kΩ")
      (description "电阻类型:厚膜电阻;阻值:22kΩ;精度:±1%;功率:62.5mW;温度系数:±100ppm/℃;")
      (fields
        (field (name "NAME") "22kΩ")
        (field (name "MANUFACTURER") "UNI-ROYAL(厚声)")
        (field (name "MANUFACTURER PART") "0402WGF2202TCE")
      )
      (libsource (lib "altium-import") (part "root_1_0402WGF2202TCE_"))
    )
    (comp (ref "R190")
      (value "33Ω")
      (description "电阻类型:厚膜电阻;阻值:33Ω;精度:±1%;功率:62.5mW;温度系数:±100ppm/℃;")
      (fields
        (field (name "NAME") "33Ω")
        (field (name "MANUFACTURER") "UNI-ROYAL(厚声)")
        (field (name "MANUFACTURER PART") "0402WGF330JTCE")
      )
      (libsource (lib "altium-import") (part "root_1_0402WGF330JTCE_"))
    )
    (comp (ref "R191")
      (value "100kΩ")
      (description "电阻类型:厚膜电阻;阻值:100kΩ;精度:±1%;功率:62.5mW;")
      (fields
        (field (name "NAME") "100kΩ")
        (field (name "MANUFACTURER") "UNI-ROYAL(厚声)")
        (field (name "MANUFACTURER PART") "0402WGF1003TCE")
      )
      (libsource (lib "altium-import") (part "root_1_0402WGF1003TCE_"))
    )
    (comp (ref "R192")
      (value "100kΩ")
      (description "电阻类型:厚膜电阻;阻值:100kΩ;精度:±1%;功率:62.5mW;")
      (fields
        (field (name "NAME") "100kΩ")
        (field (name "MANUFACTURER") "UNI-ROYAL(厚声)")
        (field (name "MANUFACTURER PART") "0402WGF1003TCE")
      )
      (libsource (lib "altium-import") (part "root_1_0402WGF1003TCE_"))
    )
    (comp (ref "R193")
      (value "1kΩ")
      (description "电阻类型:厚膜电阻;阻值:1kΩ;精度:±1%;功率:62.5mW;")
      (fields
        (field (name "NAME") "1kΩ")
        (field (name "MANUFACTURER") "UNI-ROYAL(厚声)")
        (field (name "MANUFACTURER PART") "0402WGF1001TCE")
      )
      (libsource (lib "altium-import") (part "root_0_0402WGF1001TCE_"))
    )
    (comp (ref "R194")
      (value "10kΩ")
      (description "电阻类型:厚膜电阻;阻值:10kΩ;精度:±1%;功率:62.5mW;温度系数:±100ppm/℃;")
      (fields
        (field (name "NAME") "10kΩ")
        (field (name "MANUFACTURER") "UNI-ROYAL(厚声)")
        (field (name "MANUFACTURER PART") "0402WGF1002TCE")
      )
      (libsource (lib "altium-import") (part "root_1_0402WGF1002TCE_"))
    )
    (comp (ref "R195")
      (value "1kΩ")
      (description "电阻类型:厚膜电阻;阻值:1kΩ;精度:±1%;功率:62.5mW;")
      (fields
        (field (name "NAME") "1kΩ")
        (field (name "MANUFACTURER") "UNI-ROYAL(厚声)")
        (field (name "MANUFACTURER PART") "0402WGF1001TCE")
      )
      (libsource (lib "altium-import") (part "root_1_0402WGF1001TCE_"))
    )
    (comp (ref "R196")
      (value "33Ω")
      (description "电阻类型:厚膜电阻;阻值:33Ω;精度:±1%;功率:62.5mW;温度系数:±100ppm/℃;")
      (fields
        (field (name "NAME") "33Ω")
        (field (name "MANUFACTURER") "UNI-ROYAL(厚声)")
        (field (name "MANUFACTURER PART") "0402WGF330JTCE")
      )
      (libsource (lib "altium-import") (part "root_1_0402WGF330JTCE_"))
    )
    (comp (ref "R197")
      (value "1kΩ")
      (description "电阻类型:厚膜电阻;阻值:1kΩ;精度:±1%;功率:62.5mW;")
      (fields
        (field (name "NAME") "1kΩ")
        (field (name "MANUFACTURER") "UNI-ROYAL(厚声)")
        (field (name "MANUFACTURER PART") "0402WGF1001TCE")
      )
      (libsource (lib "altium-import") (part "root_1_0402WGF1001TCE_"))
    )
    (comp (ref "SW7")
      (value "TS-1185-C-A-A-A")
      (description "触点电流:50mA;额定电压(DC):12V;绝缘电阻:-;电路结构:单刀单掷;安装方式:立贴;带灯:无;作用力:260gf;机械寿命:10万次;带支架:否;")
      (fields (field (name "MANUFACTURER") "XKB Connectivity(中国星坤)"))
      (libsource (lib "altium-import") (part "root_0_TS-1185-C-A-A-A_"))
    )
    (comp (ref "SW8")
      (value "TS-1185-C-A-A-A")
      (description "触点电流:50mA;额定电压(DC):12V;绝缘电阻:-;电路结构:单刀单掷;安装方式:立贴;带灯:无;作用力:260gf;机械寿命:10万次;带支架:否;")
      (fields (field (name "MANUFACTURER") "XKB Connectivity(中国星坤)"))
      (libsource (lib "altium-import") (part "root_0_TS-1185-C-A-A-A_"))
    )
    (comp (ref "U1")
      (value "SY8368AQQC")
      (fields (field (name "NAME") "SY8368AQQC") (field (name "MANUFACTURER") "silergy(矽力杰)"))
      (libsource (lib "altium-import") (part "root_0_SY8368AQQC_"))
    )
    (comp (ref "U2")
      (value "SY8883DFC")
      (fields (field (name "NAME") "SY8883DFC") (field (name "MANUFACTURER") "silergy(矽力杰)"))
      (libsource (lib "altium-import") (part "root_0_SY8883DFC_"))
    )
    (comp (ref "U6")
      (value "STM32H723VGH6")
      (description "应用领域:-;CPU内核:ARM-M系列;CPU最大主频:550MHz;工作电压范围:1.62V~3.6V;程序存储容量:1MB;程序存储器类型:-;RAM总容量:-;GPIO端口数量:80;")
      (fields (field (name "NAME") "STM32H723VGH6") (field (name "MANUFACTURER") "ST(意法半导体)"))
      (libsource (lib "altium-import") (part "root_0_STM32H723VGH6_"))
    )
    (comp (ref "U7")
      (value "TJA1051T/CM,118")
      (fields (field (name "NAME") "TJA1051T/CM,118") (field (name "MANUFACTURER") "NXP(恩智浦)"))
      (libsource (lib "altium-import") (part "root_0_TJA1051T/CM,118_"))
    )
    (comp (ref "U8")
      (value "TJA1051T/CM,118")
      (fields (field (name "NAME") "TJA1051T/CM,118") (field (name "MANUFACTURER") "NXP(恩智浦)"))
      (libsource (lib "altium-import") (part "root_0_TJA1051T/CM,118_"))
    )
    (comp (ref "U9")
      (value "TJA1051T/CM,118")
      (fields (field (name "NAME") "TJA1051T/CM,118") (field (name "MANUFACTURER") "NXP(恩智浦)"))
      (libsource (lib "altium-import") (part "root_0_TJA1051T/CM,118_"))
    )
    (comp (ref "U10")
      (value "BMI088")
      (fields (field (name "NAME") "BMI088") (field (name "MANUFACTURER") "Bosch(博世)"))
      (libsource (lib "altium-import") (part "root_0_BMI088_"))
    )
    (comp (ref "U11")
      (value "IST8310")
      (fields (field (name "NAME") "IST8310"))
      (libsource (lib "altium-import") (part "root_0_IST8310_"))
    )
    (comp (ref "U19")
      (value "PMBT3904")
      (fields (field (name "NAME") "PMBT3904") (field (name "MANUFACTURER") "PAKER(派克微)"))
      (libsource (lib "altium-import") (part "root_0_PMBT3904_"))
    )
    (comp (ref "U25")
      (value "SGM3157")
      (description "开关电路:-;")
      (fields (field (name "NAME") "SGM3157") (field (name "MANUFACTURER") "UMW(广东友台半导体)"))
      (libsource (lib "altium-import") (part "root_0_SGM3157_"))
    )
    (comp (ref "U27")
      (value "20009-UCAF001-X")
      (fields (field (name "NAME") "20009-UCAF001-X") (field (name "MANUFACTURER") "MINTRON(明硕)"))
      (libsource (lib "altium-import") (part "root_0_20009-UCAF001-X_"))
    )
    (comp (ref "U29")
      (value "ESP32-S3-WROOM-1U-N8")
      (fields (field (name "NAME") "ESP32-S3-WROOM-1U-N8") (field (name "MANUFACTURER") "ESPRESSIF(乐鑫)"))
      (libsource (lib "altium-import") (part "root_0_ESP32-S3-WROOM-1U-N8_"))
    )
    (comp (ref "U30")
      (value "AP2716QD")
      (description "类型:1个N沟道和1个P沟道;漏源电压(Vdss):40V;连续漏极电流(Id):16A;导通电阻(RDS(on)@Vgs,Id):44mΩ@20V,16A;")
      (fields (field (name "NAME") "AP2716QD") (field (name "MANUFACTURER") "ALLPOWER(铨力)"))
      (libsource (lib "altium-import") (part "root_0_mirrored_AP2716QD_"))
    )
    (comp (ref "U31")
      (value "SMF28CA")
      (description "极性:双向;反向截止电压(Vrwm):28V;击穿电压:31.1V;反向漏电流(Ir):1uA;峰值脉冲电流(Ipp)@10/1000μs:4.4A;最大钳位电压:45.4V;")
      (fields (field (name "NAME") "SMF28CA") (field (name "MANUFACTURER") "GOODWORK(固得沃克)"))
      (libsource (lib "altium-import") (part "root_1_SMF28CA_C2943767_"))
    )
    (comp (ref "X10")
      (value "GH125-S02DCA-00")
      (description "参考系列:-;间距:1.25mm;插针结构:1x2P;排数:1;每排PIN数:2;行距:-;公母:公型插针;安装方式:卧贴;额定电流:1A;工作温度范围:-25℃~+85℃;")
      (fields (field (name "MANUFACTURER") "JS(钜硕电子)"))
      (libsource (lib "altium-import") (part "root_0_GH125-S02DCA-00_"))
    )
    (comp (ref "X11")
      (value "GH125-S02DCA-00")
      (description "参考系列:-;间距:1.25mm;插针结构:1x2P;排数:1;每排PIN数:2;行距:-;公母:公型插针;安装方式:卧贴;额定电流:1A;工作温度范围:-25℃~+85℃;")
      (fields (field (name "MANUFACTURER") "JS(钜硕电子)"))
      (libsource (lib "altium-import") (part "root_0_GH125-S02DCA-00_"))
    )
    (comp (ref "X12")
      (value "GH125-S02DCA-00")
      (description "参考系列:-;间距:1.25mm;插针结构:1x2P;排数:1;每排PIN数:2;行距:-;公母:公型插针;安装方式:卧贴;额定电流:1A;工作温度范围:-25℃~+85℃;")
      (fields (field (name "MANUFACTURER") "JS(钜硕电子)"))
      (libsource (lib "altium-import") (part "root_0_GH125-S02DCA-00_"))
    )
    (comp (ref "X13")
      (value "25MHz")
      (description "频率:25MHz;频率公差:±10ppm;负载电容:12pF;")
      (fields
        (field (name "NAME") "25MHz")
        (field (name "MANUFACTURER") "YXC(扬兴晶振)")
        (field (name "MANUFACTURER PART") "X322525MOB4SI")
      )
      (libsource (lib "altium-import") (part "root_1_X322525MOB4SI_"))
    )
    (comp (ref "X15")
      (value "GH125-S03DCA-00")
      (description "参考系列:-;间距:1.25mm;插针结构:1x3P;排数:1;每排PIN数:3;行距:-;公母:公型插针;安装方式:卧贴;额定电流:1A;工作温度范围:-25℃~+85℃;")
      (fields (field (name "NAME") "GH125-S03DCA-00") (field (name "MANUFACTURER") "JS(钜硕电子)"))
      (libsource (lib "altium-import") (part "root_0_GH125-S03DCA-00_"))
    )
    (comp (ref "X16")
      (value "GH125-S04CCA-00")
      (description "参考系列:-;间距:1.25mm;插针结构:1x4P;排数:1;每排PIN数:4;行距:-;公母:公型插针;安装方式:立贴;额定电流:1A;工作温度范围:-25℃~+85℃;")
      (fields (field (name "NAME") "GH125-S04CCA-00") (field (name "MANUFACTURER") "JS(钜硕电子)"))
      (libsource (lib "altium-import") (part "root_0_GH125-S04CCA-00_"))
    )
    (comp (ref "X17")
      (value "GH125-S06CCA-00")
      (description "参考系列:-;间距:1.25mm;插针结构:1x6P;排数:1;每排PIN数:6;行距:-;公母:公型插针;安装方式:立贴;额定电流:1A;工作温度范围:-25℃~+85℃;")
      (fields (field (name "NAME") "GH125-S06CCA-00") (field (name "MANUFACTURER") "JS(钜硕电子)"))
      (libsource (lib "altium-import") (part "root_0_GH125-S06CCA-00_"))
    )
    (comp (ref "X18")
      (value "GH125-S04CCA-00")
      (description "参考系列:-;间距:1.25mm;插针结构:1x4P;排数:1;每排PIN数:4;行距:-;公母:公型插针;安装方式:立贴;额定电流:1A;工作温度范围:-25℃~+85℃;")
      (fields (field (name "NAME") "GH125-S04CCA-00") (field (name "MANUFACTURER") "JS(钜硕电子)"))
      (libsource (lib "altium-import") (part "root_0_GH125-S04CCA-00_"))
    )
    (comp (ref "X19")
      (value "GH125-S04CCA-00")
      (description "参考系列:-;间距:1.25mm;插针结构:1x4P;排数:1;每排PIN数:4;行距:-;公母:公型插针;安装方式:立贴;额定电流:1A;工作温度范围:-25℃~+85℃;")
      (fields (field (name "NAME") "GH125-S04CCA-00") (field (name "MANUFACTURER") "JS(钜硕电子)"))
      (libsource (lib "altium-import") (part "root_0_GH125-S04CCA-00_"))
    )
  )
  (nets
    (net (code "1") (name "+3.3V") (class "Default")
      (node (ref "BUZZER3") (pin "1") (pinfunction "+_1") (pintype "passive"))
      (node (ref "C106") (pin "2") (pinfunction "2_2") (pintype "passive"))
      (node (ref "C107") (pin "2") (pinfunction "2_2") (pintype "passive"))
      (node (ref "C108") (pin "2") (pinfunction "2_2") (pintype "passive"))
      (node (ref "C109") (pin "2") (pinfunction "2_2") (pintype "passive"))
      (node (ref "C110") (pin "2") (pinfunction "2_2") (pintype "passive"))
      (node (ref "C111") (pin "2") (pinfunction "2_2") (pintype "passive"))
      (node (ref "C112") (pin "2") (pinfunction "2_2") (pintype "passive"))
      (node (ref "C118") (pin "1") (pinfunction "1_1") (pintype "passive"))
      (node (ref "C119") (pin "2") (pinfunction "2_2") (pintype "passive"))
      (node (ref "C120") (pin "2") (pinfunction "2_2") (pintype "passive"))
      (node (ref "C121") (pin "2") (pinfunction "2_2") (pintype "passive"))
      (node (ref "C122") (pin "2") (pinfunction "2_2") (pintype "passive"))
      (node (ref "C123") (pin "2") (pinfunction "2_2") (pintype "passive"))
      (node (ref "C14") (pin "2") (pinfunction "2_2") (pintype "passive"))
      (node (ref "C18") (pin "2") (pinfunction "2_2") (pintype "passive"))
      (node (ref "C75") (pin "2") (pinfunction "2_2") (pintype "passive"))
      (node (ref "D8") (pin "1") (pinfunction "K_1") (pintype "passive"))
      (node (ref "D9") (pin "2") (pinfunction "2_2") (pintype "passive"))
      (node (ref "L2") (pin "2") (pinfunction "2_2") (pintype "passive"))
      (node (ref "LED2") (pin "2") (pinfunction "A_2") (pintype "passive"))
      (node (ref "LED3") (pin "2") (pinfunction "A_2") (pintype "passive"))
      (node (ref "LED4") (pin "2") (pinfunction "+_2") (pintype "passive"))
      (node (ref "LED5") (pin "2") (pinfunction "A_2") (pintype "passive"))
      (node (ref "R119") (pin "2") (pinfunction "2_2") (pintype "passive"))
      (node (ref "R120") (pin "2") (pinfunction "2_2") (pintype "passive"))
      (node (ref "R121") (pin "2") (pinfunction "2_2") (pintype "passive"))
      (node (ref "R144") (pin "2") (pinfunction "2_2") (pintype "passive"))
      (node (ref "R146") (pin "2") (pinfunction "2_2") (pintype "passive"))
      (node (ref "R16") (pin "1") (pinfunction "1_1") (pintype "passive"))
      (node (ref "R182") (pin "2") (pinfunction "2_2") (pintype "passive"))
      (node (ref "U10") (pin "11") (pinfunction "VDDIO_11") (pintype "passive"))
      (node (ref "U10") (pin "3") (pinfunction "VDD_3") (pintype "passive"))
      (node (ref "U11") (pin "13") (pinfunction "DVDD_13") (pintype "passive"))
      (node (ref "U11") (pin "2") (pinfunction "AVDD_2") (pintype "passive"))
      (node (ref "U25") (pin "5") (pinfunction "VCC_5") (pintype "passive"))
      (node (ref "U29") (pin "2") (pinfunction "3V3_2") (pintype "passive"))
      (node (ref "U6") (pin "B2") (pinfunction "VBAT_B2") (pintype "passive"))
      (node (ref "U6") (pin "D2") (pinfunction "VDD_D2") (pintype "passive"))
      (node (ref "U6") (pin "F4") (pinfunction "VDD_F4") (pintype "passive"))
      (node (ref "U6") (pin "F5") (pinfunction "VDD_F5") (pintype "passive"))
      (node (ref "U6") (pin "F6") (pinfunction "VDD33USB_F6") (pintype "passive"))
      (node (ref "U6") (pin "H1") (pinfunction "VDDA_H1") (pintype "passive"))
      (node (ref "U6") (pin "K1") (pinfunction "VDD_K1") (pintype "passive"))
      (node (ref "X16") (pin "1") (pinfunction "1_1") (pintype "passive"))
      (node (ref "X17") (pin "1") (pinfunction "1_1") (pintype "passive"))
    )
    (net (code "2") (name "+5V") (class "Default")
      (node (ref "C113") (pin "1") (pinfunction "1_1") (pintype "passive"))
      (node (ref "C114") (pin "1") (pinfunction "1_1") (pintype "passive"))
      (node (ref "C115") (pin "1") (pinfunction "1_1") (pintype "passive"))
      (node (ref "C117") (pin "2") (pinfunction "2_2") (pintype "passive"))
      (node (ref "C13") (pin "2") (pinfunction "2_2") (pintype "passive"))
      (node (ref "C15") (pin "2") (pinfunction "2_2") (pintype "passive"))
      (node (ref "C16") (pin "2") (pinfunction "2_2") (pintype "passive"))
      (node (ref "C17") (pin "2") (pinfunction "2_2") (pintype "passive"))
      (node (ref "C8") (pin "2") (pinfunction "2_2") (pintype "passive"))
      (node (ref "CN15") (pin "4") (pinfunction "4_4") (pintype "passive"))
      (node (ref "CN16") (pin "4") (pinfunction "4_4") (pintype "passive"))
      (node (ref "CN17") (pin "4") (pinfunction "4_4") (pintype "passive"))
      (node (ref "CN5") (pin "1") (pinfunction "1_1") (pintype "passive"))
      (node (ref "H10") (pin "2") (pinfunction "2_2") (pintype "passive"))
      (node (ref "H4") (pin "2") (pinfunction "2_2") (pintype "passive"))
      (node (ref "H5") (pin "2") (pinfunction "2_2") (pintype "passive"))
      (node (ref "H6") (pin "2") (pinfunction "2_2") (pintype "passive"))
      (node (ref "H7") (pin "2") (pinfunction "2_2") (pintype "passive"))
      (node (ref "H8") (pin "2") (pinfunction "2_2") (pintype "passive"))
      (node (ref "H9") (pin "2") (pinfunction "2_2") (pintype "passive"))
      (node (ref "L1") (pin "1") (pinfunction "1_1") (pintype "passive"))
      (node (ref "LED6") (pin "3") (pinfunction "VDD_3") (pintype "passive"))
      (node (ref "LED7") (pin "1") (pinfunction "+_1") (pintype "passive"))
      (node (ref "LED7") (pin "3") (pinfunction "+_3") (pintype "passive"))
      (node (ref "R13") (pin "1") (pinfunction "1_1") (pintype "passive"))
      (node (ref "R177") (pin "2") (pinfunction "2_2") (pintype "passive"))
      (node (ref "R178") (pin "2") (pinfunction "2_2") (pintype "passive"))
      (node (ref "R179") (pin "2") (pinfunction "2_2") (pintype "passive"))
      (node (ref "R180") (pin "2") (pinfunction "2_2") (pintype "passive"))
      (node (ref "R9") (pin "2") (pinfunction "2_2") (pintype "passive"))
      (node (ref "U2") (pin "3") (pinfunction "IN_3") (pintype "passive"))
      (node (ref "U2") (pin "7") (pinfunction "EN_7") (pintype "passive"))
      (node (ref "U27") (pin "A4") (pinfunction "VBUS_A4") (pintype "passive"))
      (node (ref "U27") (pin "A9") (pinfunction "VBUS_A9") (pintype "passive"))
      (node (ref "U27") (pin "B4") (pinfunction "VBUS_B4") (pintype "passive"))
      (node (ref "U27") (pin "B9") (pinfunction "VBUS_B9") (pintype "passive"))
      (node (ref "U7") (pin "3") (pinfunction "VCC_3") (pintype "passive"))
      (node (ref "U8") (pin "3") (pinfunction "VCC_3") (pintype "passive"))
      (node (ref "U9") (pin "3") (pinfunction "VCC_3") (pintype "passive"))
      (node (ref "X18") (pin "1") (pinfunction "1_1") (pintype "passive"))
      (node (ref "X19") (pin "1") (pinfunction "1_1") (pintype "passive"))
    )
    (net (code "3") (name "+24V") (class "Default")
      (node (ref "C127") (pin "1") (pinfunction "1_1") (pintype "passive"))
      (node (ref "R11") (pin "2") (pinfunction "2_2") (pintype "passive"))
      (node (ref "R188") (pin "2") (pinfunction "2_2") (pintype "passive"))
      (node (ref "R196") (pin "2") (pinfunction "2_2") (pintype "passive"))
      (node (ref "U1") (pin "4") (pinfunction "IN_4") (pintype "passive"))
      (node (ref "U1") (pin "5") (pinfunction "IN_5") (pintype "passive"))
      (node (ref "U1") (pin "6") (pinfunction "IN_6") (pintype "passive"))
      (node (ref "U30") (pin "10") (pinfunction "D1_10") (pintype "passive"))
      (node (ref "U30") (pin "5") (pinfunction "D1_5") (pintype "passive"))
      (node (ref "U30") (pin "6") (pinfunction "D1_6") (pintype "passive"))
    )
    (net (code "4") (name "+24V_BAT") (class "Default")
      (node (ref "C125") (pin "2") (pinfunction "2_2") (pintype "passive"))
      (node (ref "C126") (pin "2") (pinfunction "2_2") (pintype "passive"))
      (node (ref "CN11") (pin "2") (pinfunction "2_2") (pintype "passive"))
      (node (ref "Q7") (pin "2") (pinfunction "E_2") (pintype "passive"))
      (node (ref "R190") (pin "2") (pinfunction "2_2") (pintype "passive"))
      (node (ref "R191") (pin "2") (pinfunction "2_2") (pintype "passive"))
      (node (ref "R192") (pin "2") (pinfunction "2_2") (pintype "passive"))
      (node (ref "U30") (pin "3") (pinfunction "S1_3") (pintype "passive"))
      (node (ref "U31") (pin "2") (pinfunction "2_2") (pintype "passive"))
    )
    (net (code "5") (name "/ADC_BAT") (class "Default")
      (node (ref "C124") (pin "2") (pinfunction "2_2") (pintype "passive"))
      (node (ref "D9") (pin "3") (pinfunction "3_3") (pintype "passive"))
      (node (ref "R188") (pin "1") (pinfunction "1_1") (pintype "passive"))
      (node (ref "R189") (pin "2") (pinfunction "2_2") (pintype "passive"))
      (node (ref "U6") (pin "H3") (pinfunction "PA5_H3") (pintype "passive"))
    )
    (net (code "6") (name "/BOOT0") (class "Default")
      (node (ref "R118") (pin "2") (pinfunction "2_2") (pintype "passive"))
      (node (ref "U6") (pin "D5") (pinfunction "BOOT0_D5") (pintype "passive"))
    )
    (net (code "7") (name "/BS") (class "Default")
      (node (ref "C7") (pin "1") (pinfunction "1_1") (pintype "passive"))
      (node (ref "L1") (pin "2") (pinfunction "2_2") (pintype "passive"))
      (node (ref "U1") (pin "2") (pinfunction "LX_2") (pintype "passive"))
    )
    (net (code "8") (name "/CAN1H") (class "Default")
      (node (ref "R79") (pin "2") (pinfunction "2_2") (pintype "passive"))
      (node (ref "U9") (pin "7") (pinfunction "CANH_7") (pintype "passive"))
      (node (ref "X12") (pin "2") (pinfunction "2_2") (pintype "passive"))
    )
    (net (code "9") (name "/CAN1L") (class "Default")
      (node (ref "R79") (pin "1") (pinfunction "1_1") (pintype "passive"))
      (node (ref "U9") (pin "6") (pinfunction "CANL_6") (pintype "passive"))
      (node (ref "X12") (pin "1") (pinfunction "1_1") (pintype "passive"))
    )
    (net (code "10") (name "/CAN1_RXD") (class "Default")
      (node (ref "U6") (pin "B4") (pinfunction "PB8_B4") (pintype "passive"))
      (node (ref "U9") (pin "4") (pinfunction "RXD_4") (pintype "passive"))
    )
    (net (code "11") (name "/CAN1_TXD") (class "Default")
      (node (ref "U6") (pin "A4") (pinfunction "PB9_A4") (pintype "passive"))
      (node (ref "U9") (pin "1") (pinfunction "TXD_1") (pintype "passive"))
    )
    (net (code "12") (name "/CAN2H") (class "Default")
      (node (ref "R80") (pin "2") (pinfunction "2_2") (pintype "passive"))
      (node (ref "U8") (pin "7") (pinfunction "CANH_7") (pintype "passive"))
      (node (ref "X11") (pin "2") (pinfunction "2_2") (pintype "passive"))
    )
    (net (code "13") (name "/CAN2L") (class "Default")
      (node (ref "R80") (pin "1") (pinfunction "1_1") (pintype "passive"))
      (node (ref "U8") (pin "6") (pinfunction "CANL_6") (pintype "passive"))
      (node (ref "X11") (pin "1") (pinfunction "1_1") (pintype "passive"))
    )
    (net (code "14") (name "/CAN2_RXD") (class "Default")
      (node (ref "U6") (pin "C5") (pinfunction "PB5_C5") (pintype "passive"))
      (node (ref "U8") (pin "4") (pinfunction "RXD_4") (pintype "passive"))
    )
    (net (code "15") (name "/CAN2_TXD") (class "Default")
      (node (ref "U6") (pin "B5") (pinfunction "PB6_B5") (pintype "passive"))
      (node (ref "U8") (pin "1") (pinfunction "TXD_1") (pintype "passive"))
    )
    (net (code "16") (name "/CAN3H") (class "Default")
      (node (ref "R81") (pin "2") (pinfunction "2_2") (pintype "passive"))
      (node (ref "U7") (pin "7") (pinfunction "CANH_7") (pintype "passive"))
      (node (ref "X10") (pin "2") (pinfunction "2_2") (pintype "passive"))
    )
    (net (code "17") (name "/CAN3L") (class "Default")
      (node (ref "R81") (pin "1") (pinfunction "1_1") (pintype "passive"))
      (node (ref "U7") (pin "6") (pinfunction "CANL_6") (pintype "passive"))
      (node (ref "X10") (pin "1") (pinfunction "1_1") (pintype "passive"))
    )
    (net (code "18") (name "/CAN3_RXD") (class "Default")
      (node (ref "U6") (pin "K10") (pinfunction "PD12_K10") (pintype "passive"))
      (node (ref "U7") (pin "4") (pinfunction "RXD_4") (pintype "passive"))
    )
    (net (code "19") (name "/CAN3_TXD") (class "Default")
      (node (ref "U6") (pin "J10") (pinfunction "PD13_J10") (pintype "passive"))
      (node (ref "U7") (pin "1") (pinfunction "TXD_1") (pintype "passive"))
    )
    (net (code "20") (name "/CS1_Accel") (class "Default")
      (node (ref "U10") (pin "14") (pinfunction "CSB1_14") (pintype "passive"))
      (node (ref "U6") (pin "G3") (pinfunction "PA4_G3") (pintype "passive"))
    )
    (net (code "21") (name "/CS1_Gyro") (class "Default")
      (node (ref "U10") (pin "5") (pinfunction "CSB2_5") (pintype "passive"))
      (node (ref "U6") (pin "J4") (pinfunction "PB0_J4") (pintype "passive"))
    )
    (net (code "22") (name "/DBUS") (class "Default")
      (node (ref "R145") (pin "1") (pinfunction "1_1") (pintype "passive"))
      (node (ref "U19") (pin "1") (pinfunction "B_1") (pintype "passive"))
    )
    (net (code "23") (name "/DIO") (class "Default")
      (node (ref "R135") (pin "2") (pinfunction "2_2") (pintype "passive"))
      (node (ref "U25") (pin "4") (pinfunction "A_4") (pintype "passive"))
      (node (ref "U6") (pin "A10") (pinfunction "PA13_A10") (pintype "passive"))
    )
    (net (code "24") (name "/DIO_C") (class "Default")
      (node (ref "R135") (pin "1") (pinfunction "1_1") (pintype "passive"))
      (node (ref "U25") (pin "6") (pinfunction "Select_6") (pintype "passive"))
      (node (ref "U29") (pin "29") (pinfunction "IO36_29") (pintype "passive"))
    )
    (net (code "25") (name "/DIO_I") (class "Default")
      (node (ref "U25") (pin "1") (pinfunction "B1_1") (pintype "passive"))
      (node (ref "U29") (pin "28") (pinfunction "IO35_28") (pintype "passive"))
    )
    (net (code "26") (name "/DIO_O") (class "Default")
      (node (ref "U25") (pin "3") (pinfunction "B0_3") (pintype "passive"))
      (node (ref "U29") (pin "24") (pinfunction "IO47_24") (pintype "passive"))
    )
    (net (code "27") (name "/DRDY_IST8310") (class "Default")
      (node (ref "U11") (pin "15") (pinfunction "DRDY_15") (pintype "passive"))
      (node (ref "U6") (pin "G6") (pinfunction "PE10_G6") (pintype "passive"))
    )
    (net (code "28") (name "/EN") (class "Default")
      (node (ref "C96") (pin "2") (pinfunction "2_2") (pintype "passive"))
      (node (ref "R144") (pin "1") (pinfunction "1_1") (pintype "passive"))
      (node (ref "U29") (pin "3") (pinfunction "EN_3") (pintype "passive"))
    )
    (net (code "29") (name "/ESP_DN") (class "Default")
      (node (ref "U27") (pin "A7") (pinfunction "DN1_A7") (pintype "passive"))
      (node (ref "U27") (pin "B7") (pinfunction "DN2_B7") (pintype "passive"))
      (node (ref "U29") (pin "13") (pinfunction "IO19_13") (pintype "passive"))
    )
    (net (code "30") (name "/ESP_DP") (class "Default")
      (node (ref "U27") (pin "A6") (pinfunction "DP1_A6") (pintype "passive"))
      (node (ref "U27") (pin "B6") (pinfunction "DP2_B6") (pintype "passive"))
      (node (ref "U29") (pin "14") (pinfunction "IO20_14") (pintype "passive"))
    )
    (net (code "31") (name "/ESP_LED") (class "Default")
      (node (ref "LED6") (pin "2") (pinfunction "DI_2") (pintype "passive"))
      (node (ref "U29") (pin "25") (pinfunction "IO48_25") (pintype "passive"))
    )
    (net (code "32") (name "/FB") (class "Default")
      (node (ref "R10") (pin "2") (pinfunction "2_2") (pintype "passive"))
      (node (ref "R8") (pin "1") (pinfunction "1_1") (pintype "passive"))
      (node (ref "R9") (pin "1") (pinfunction "1_1") (pintype "passive"))
      (node (ref "U1") (pin "9") (pinfunction "FB_9") (pintype "passive"))
    )
    (net (code "33") (name "/FB5V") (class "Default")
      (node (ref "C14") (pin "1") (pinfunction "1_1") (pintype "passive"))
      (node (ref "R15") (pin "2") (pinfunction "2_2") (pintype "passive"))
      (node (ref "R16") (pin "2") (pinfunction "2_2") (pintype "passive"))
      (node (ref "U2") (pin "1") (pinfunction "FB_1") (pintype "passive"))
    )
    (net (code "34") (name "/GPIO0") (class "Default")
      (node (ref "SW7") (pin "2") (pinfunction "2_2") (pintype "passive"))
      (node (ref "U29") (pin "27") (pinfunction "IO0_27") (pintype "passive"))
    )
    (net (code "35") (name "/I2C2_SCL") (class "Default")
      (node (ref "U6") (pin "J7") (pinfunction "PB10_J7") (pintype "passive"))
      (node (ref "X16") (pin "4") (pinfunction "4_4") (pintype "passive"))
    )
    (net (code "36") (name "/I2C2_SDA") (class "Default")
      (node (ref "U6") (pin "K7") (pinfunction "PB11_K7") (pintype "passive"))
      (node (ref "X16") (pin "3") (pinfunction "3_3") (pintype "passive"))
    )
    (net (code "37") (name "/I2C3_SCL") (class "Default")
      (node (ref "R182") (pin "1") (pinfunction "1_1") (pintype "passive"))
      (node (ref "U11") (pin "1") (pinfunction "SCL_1") (pintype "passive"))
      (node (ref "U6") (pin "D9") (pinfunction "PA8_D9") (pintype "passive"))
    )
    (net (code "38") (name "/I2C3_SDA") (class "Default")
      (node (ref "R121") (pin "1") (pinfunction "1_1") (pintype "passive"))
      (node (ref "U11") (pin "16") (pinfunction "SDA_16") (pintype "passive"))
      (node (ref "U6") (pin "E9") (pinfunction "PC9_E9") (pintype "passive"))
    )
    (net (code "39") (name "/INT1_Accel") (class "Default")
      (node (ref "U10") (pin "16") (pinfunction "INT1_16") (pintype "passive"))
      (node (ref "U6") (pin "G4") (pinfunction "PC4_G4") (pintype "passive"))
    )
    (net (code "40") (name "/INT1_Gyro") (class "Default")
      (node (ref "U10") (pin "12") (pinfunction "INT3_12") (pintype "passive"))
      (node (ref "U6") (pin "H4") (pinfunction "PC5_H4") (pintype "passive"))
    )
    (net (code "41") (name "/KEY") (class "Default")
      (node (ref "SW8") (pin "2") (pinfunction "2_2") (pintype "passive"))
      (node (ref "U29") (pin "23") (pinfunction "IO21_23") (pintype "passive"))
    )
    (net (code "42") (name "/NG2") (class "Default")
      (node (ref "D10") (pin "1") (pinfunction "K_1") (pintype "passive"))
      (node (ref "R191") (pin "1") (pinfunction "1_1") (pintype "passive"))
      (node (ref "U30") (pin "2") (pinfunction "G2_2") (pintype "passive"))
    )
    (net (code "43") (name "/NRST") (class "Default")
      (node (ref "C104") (pin "2") (pinfunction "2_2") (pintype "passive"))
      (node (ref "KEY2") (pin "1") (pinfunction "1_1") (pintype "passive"))
      (node (ref "R119") (pin "1") (pinfunction "1_1") (pintype "passive"))
      (node (ref "U29") (pin "33") (pinfunction "IO40_33") (pintype "passive"))
      (node (ref "U6") (pin "E1") (pinfunction "NRST_E1") (pintype "passive"))
    )
    (net (code "44") (name "/OSC32_IN") (class "Default")
      (node (ref "U6") (pin "A1") (pinfunction "PC14-OSC32_IN_A1") (pintype "passive"))
    )
    (net (code "45") (name "/OSC32_OUT") (class "Default")
      (node (ref "U6") (pin "B1") (pinfunction "PC15-OSC32_OUT_B1") (pintype "passive"))
    )
    (net (code "46") (name "/OSC_IN") (class "Default")
      (node (ref "C49") (pin "2") (pinfunction "2_2") (pintype "passive"))
      (node (ref "U6") (pin "C1") (pinfunction "PH0-OSC_IN_C1") (pintype "passive"))
      (node (ref "X13") (pin "3") (pinfunction "OSC2_3") (pintype "passive"))
    )
    (net (code "47") (name "/OSC_OUT") (class "Default")
      (node (ref "C48") (pin "1") (pinfunction "1_1") (pintype "passive"))
      (node (ref "U6") (pin "D1") (pinfunction "PH1-OSC_OUT_D1") (pintype "passive"))
      (node (ref "X13") (pin "1") (pinfunction "OSC1_1") (pintype "passive"))
    )
    (net (code "48") (name "/PA0") (class "Default")
      (node (ref "H5") (pin "1") (pinfunction "1_1") (pintype "passive"))
      (node (ref "U6") (pin "G2") (pinfunction "PA0_G2") (pintype "passive"))
    )
    (net (code "49") (name "/PA1") (class "Default")
      (node (ref "H6") (pin "1") (pinfunction "1_1") (pintype "passive"))
      (node (ref "U6") (pin "H2") (pinfunction "PA1_H2") (pintype "passive"))
    )
    (net (code "50") (name "/PA2") (class "Default")
      (node (ref "H7") (pin "1") (pinfunction "1_1") (pintype "passive"))
      (node (ref "U6") (pin "J2") (pinfunction "PA2_J2") (pintype "passive"))
    )
    (net (code "51") (name "/PA3") (class "Default")
      (node (ref "H8") (pin "1") (pinfunction "1_1") (pintype "passive"))
      (node (ref "U6") (pin "K2") (pinfunction "PA3_K2") (pintype "passive"))
    )
    (net (code "52") (name "/PA6") (class "Default")
      (node (ref "R147") (pin "1") (pinfunction "1_1") (pintype "passive"))
      (node (ref "U6") (pin "J3") (pinfunction "PA6_J3") (pintype "passive"))
    )
    (net (code "53") (name "/PA7") (class "Default")
      (node (ref "R148") (pin "1") (pinfunction "1_1") (pintype "passive"))
      (node (ref "U6") (pin "K3") (pinfunction "PA7_K3") (pintype "passive"))
    )
    (net (code "54") (name "/PA10") (class "Default")
      (node (ref "R183") (pin "1") (pinfunction "1_1") (pintype "passive"))
      (node (ref "U6") (pin "D10") (pinfunction "PA10_D10") (pintype "passive"))
    )
    (net (code "55") (name "/PB1") (class "Default")
      (node (ref "H9") (pin "1") (pinfunction "1_1") (pintype "passive"))
      (node (ref "U6") (pin "K4") (pinfunction "PB1_K4") (pintype "passive"))
    )
    (net (code "56") (name "/PD14") (class "Default")
      (node (ref "R181") (pin "2") (pinfunction "2_2") (pintype "passive"))
      (node (ref "U6") (pin "H8") (pinfunction "PD14_H8") (pintype "passive"))
    )
    (net (code "57") (name "/PD15") (class "Default")
      (node (ref "H10") (pin "1") (pinfunction "1_1") (pintype "passive"))
      (node (ref "U6") (pin "G8") (pinfunction "PD15_G8") (pintype "passive"))
    )
    (net (code "58") (name "/PE9") (class "Default")
      (node (ref "R184") (pin "1") (pinfunction "1_1") (pintype "passive"))
      (node (ref "U6") (pin "K5") (pinfunction "PE9_K5") (pintype "passive"))
    )
    (net (code "59") (name "/PE11") (class "Default")
      (node (ref "R185") (pin "1") (pinfunction "1_1") (pintype "passive"))
      (node (ref "U6") (pin "H6") (pinfunction "PE11_H6") (pintype "passive"))
    )
    (net (code "60") (name "/PG1") (class "Default")
      (node (ref "R195") (pin "2") (pinfunction "2_2") (pintype "passive"))
      (node (ref "U30") (pin "4") (pinfunction "G1_4") (pintype "passive"))
    )
    (net (code "61") (name "/PG5V") (class "Default")
      (node (ref "LED1") (pin "2") (pinfunction "A_2") (pintype "passive"))
      (node (ref "U1") (pin "11") (pinfunction "PG_11") (pintype "passive"))
    )
    (net (code "62") (name "/RSTN_IST8310") (class "Default")
      (node (ref "U11") (pin "14") (pinfunction "RSTN_14") (pintype "passive"))
      (node (ref "U6") (pin "G7") (pinfunction "PE14_G7") (pintype "passive"))
    )
    (net (code "63") (name "/SPI1_MISO") (class "Default")
      (node (ref "U10") (pin "10") (pinfunction "SDO2_10") (pintype "passive"))
      (node (ref "U10") (pin "15") (pinfunction "SDO1_15") (pintype "passive"))
      (node (ref "U6") (pin "A6") (pinfunction "PB4_A6") (pintype "passive"))
    )
    (net (code "64") (name "/SPI1_MOSI") (class "Default")
      (node (ref "U10") (pin "9") (pinfunction "SDA/SDI_9") (pintype "passive"))
      (node (ref "U6") (pin "D6") (pinfunction "PD7_D6") (pintype "passive"))
    )
    (net (code "65") (name "/SPI1_SCK") (class "Default")
      (node (ref "U10") (pin "8") (pinfunction "SCL/SCK_8") (pintype "passive"))
      (node (ref "U6") (pin "A7") (pinfunction "PB3_A7") (pintype "passive"))
    )
    (net (code "66") (name "/SPI4_CS") (class "Default")
      (node (ref "U6") (pin "A2") (pinfunction "PC13_A2") (pintype "passive"))
      (node (ref "X17") (pin "6") (pinfunction "6_6") (pintype "passive"))
    )
    (net (code "67") (name "/SPI4_MISO") (class "Default")
      (node (ref "U6") (pin "D3") (pinfunction "PE5_D3") (pintype "passive"))
      (node (ref "X17") (pin "4") (pinfunction "4_4") (pintype "passive"))
    )
    (net (code "68") (name "/SPI4_MOSI") (class "Default")
      (node (ref "U6") (pin "E3") (pinfunction "PE6_E3") (pintype "passive"))
      (node (ref "X17") (pin "3") (pinfunction "3_3") (pintype "passive"))
    )
    (net (code "69") (name "/SPI4_SCK") (class "Default")
      (node (ref "U6") (pin "A3") (pinfunction "PE2_A3") (pintype "passive"))
      (node (ref "X17") (pin "5") (pinfunction "5_5") (pintype "passive"))
    )
    (net (code "70") (name "/SWCLK") (class "Default")
      (node (ref "U29") (pin "30") (pinfunction "IO37_30") (pintype "passive"))
      (node (ref "U6") (pin "A9") (pinfunction "PA14_A9") (pintype "passive"))
    )
    (net (code "71") (name "/UART1_RX") (class "Default")
      (node (ref "R186") (pin "2") (pinfunction "2_2") (pintype "passive"))
      (node (ref "U29") (pin "35") (pinfunction "IO42_35") (pintype "passive"))
      (node (ref "U6") (pin "A5") (pinfunction "PB7_A5") (pintype "passive"))
    )
    (net (code "72") (name "/UART1_TX") (class "Default")
      (node (ref "R187") (pin "2") (pinfunction "2_2") (pintype "passive"))
      (node (ref "U29") (pin "34") (pinfunction "IO41_34") (pintype "passive"))
      (node (ref "U6") (pin "C9") (pinfunction "PA9_C9") (pintype "passive"))
    )
    (net (code "73") (name "/UART2_RX") (class "Default")
      (node (ref "CN15") (pin "1") (pinfunction "1_1") (pintype "passive"))
      (node (ref "U6") (pin "C6") (pinfunction "PD6_C6") (pintype "passive"))
    )
    (net (code "74") (name "/UART2_TX") (class "Default")
      (node (ref "CN15") (pin "2") (pinfunction "2_2") (pintype "passive"))
      (node (ref "U6") (pin "B6") (pinfunction "PD5_B6") (pintype "passive"))
    )
    (net (code "75") (name "/UART3_RX") (class "Default")
      (node (ref "R146") (pin "1") (pinfunction "1_1") (pintype "passive"))
      (node (ref "U19") (pin "3") (pinfunction "C_3") (pintype "passive"))
      (node (ref "U6") (pin "B8") (pinfunction "PC11_B8") (pintype "passive"))
    )
    (net (code "76") (name "/UART4_RX") (class "Default")
      (node (ref "CN16") (pin "1") (pinfunction "1_1") (pintype "passive"))
      (node (ref "U6") (pin "C10") (pinfunction "PA11_C10") (pintype "passive"))
    )
    (net (code "77") (name "/UART4_TX") (class "Default")
      (node (ref "CN16") (pin "2") (pinfunction "2_2") (pintype "passive"))
      (node (ref "U6") (pin "B10") (pinfunction "PA12_B10") (pintype "passive"))
    )
    (net (code "78") (name "/UART5_RX") (class "Default")
      (node (ref "CN17") (pin "1") (pinfunction "1_1") (pintype "passive"))
      (node (ref "U6") (pin "B7") (pinfunction "PD2_B7") (pintype "passive"))
    )
    (net (code "79") (name "/UART5_TX") (class "Default")
      (node (ref "CN17") (pin "2") (pinfunction "2_2") (pintype "passive"))
      (node (ref "U6") (pin "C8") (pinfunction "PC12_C8") (pintype "passive"))
    )
    (net (code "80") (name "/UART6_RX") (class "Default")
      (node (ref "U6") (pin "E10") (pinfunction "PC7_E10") (pintype "passive"))
      (node (ref "X19") (pin "4") (pinfunction "4_4") (pintype "passive"))
    )
    (net (code "81") (name "/UART6_TX") (class "Default")
      (node (ref "U6") (pin "F10") (pinfunction "PC6_F10") (pintype "passive"))
      (node (ref "X19") (pin "3") (pinfunction "3_3") (pintype "passive"))
    )
    (net (code "82") (name "/UART7_RX") (class "Default")
      (node (ref "U6") (pin "H5") (pinfunction "PE7_H5") (pintype "passive"))
      (node (ref "X15") (pin "3") (pinfunction "3_3") (pintype "passive"))
    )
    (net (code "83") (name "/UART7_TX") (class "Default")
      (node (ref "U6") (pin "A8") (pinfunction "PA15_A8") (pintype "passive"))
      (node (ref "X15") (pin "2") (pinfunction "2_2") (pintype "passive"))
    )
    (net (code "84") (name "/UART8_RX") (class "Default")
      (node (ref "U6") (pin "D4") (pinfunction "PE0_D4") (pintype "passive"))
      (node (ref "X18") (pin "4") (pinfunction "4_4") (pintype "passive"))
    )
    (net (code "85") (name "/UART8_TX") (class "Default")
      (node (ref "U6") (pin "C4") (pinfunction "PE1_C4") (pintype "passive"))
      (node (ref "X18") (pin "3") (pinfunction "3_3") (pintype "passive"))
    )
    (net (code "86") (name "/UKEY") (class "Default")
      (node (ref "C105") (pin "2") (pinfunction "2_2") (pintype "passive"))
      (node (ref "KEY1") (pin "1") (pinfunction "1_1") (pintype "passive"))
      (node (ref "R120") (pin "1") (pinfunction "1_1") (pintype "passive"))
      (node (ref "U6") (pin "D8") (pinfunction "PD0_D8") (pintype "passive"))
    )
    (net (code "87") (name "<NO NET>") (class "Default")
      (node (ref "C104") (pin "1") (pinfunction "1_1") (pintype "passive"))
      (node (ref "C105") (pin "1") (pinfunction "1_1") (pintype "passive"))
      (node (ref "C106") (pin "1") (pinfunction "1_1") (pintype "passive"))
      (node (ref "C107") (pin "1") (pinfunction "1_1") (pintype "passive"))
      (node (ref "C108") (pin "1") (pinfunction "1_1") (pintype "passive"))
      (node (ref "C109") (pin "1") (pinfunction "1_1") (pintype "passive"))
      (node (ref "C110") (pin "1") (pinfunction "1_1") (pintype "passive"))
      (node (ref "C111") (pin "1") (pinfunction "1_1") (pintype "passive"))
      (node (ref "C112") (pin "1") (pinfunction "1_1") (pintype "passive"))
      (node (ref "C113") (pin "2") (pinfunction "2_2") (pintype "passive"))
      (node (ref "C114") (pin "2") (pinfunction "2_2") (pintype "passive"))
      (node (ref "C115") (pin "2") (pinfunction "2_2") (pintype "passive"))
      (node (ref "C117") (pin "1") (pinfunction "1_1") (pintype "passive"))
      (node (ref "C118") (pin "2") (pinfunction "2_2") (pintype "passive"))
      (node (ref "C119") (pin "1") (pinfunction "1_1") (pintype "passive"))
      (node (ref "C12") (pin "1") (pinfunction "1_1") (pintype "passive"))
      (node (ref "C120") (pin "1") (pinfunction "1_1") (pintype "passive"))
      (node (ref "C121") (pin "1") (pinfunction "1_1") (pintype "passive"))
      (node (ref "C122") (pin "1") (pinfunction "1_1") (pintype "passive"))
      (node (ref "C123") (pin "1") (pinfunction "1_1") (pintype "passive"))
      (node (ref "C124") (pin "1") (pinfunction "1_1") (pintype "passive"))
      (node (ref "C127") (pin "2") (pinfunction "2_2") (pintype "passive"))
      (node (ref "C13") (pin "1") (pinfunction "1_1") (pintype "passive"))
      (node (ref "C130") (pin "1") (pinfunction "1_1") (pintype "passive"))
      (node (ref "C15") (pin "1") (pinfunction "1_1") (pintype "passive"))
      (node (ref "C16") (pin "1") (pinfunction "1_1") (pintype "passive"))
      (node (ref "C17") (pin "1") (pinfunction "1_1") (pintype "passive"))
      (node (ref "C18") (pin "1") (pinfunction "1_1") (pintype "passive"))
      (node (ref "C36") (pin "1") (pinfunction "1_1") (pintype "passive"))
      (node (ref "C37") (pin "2") (pinfunction "2_2") (pintype "passive"))
      (node (ref "C48") (pin "2") (pinfunction "2_2") (pintype "passive"))
      (node (ref "C49") (pin "1") (pinfunction "1_1") (pintype "passive"))
      (node (ref "C75") (pin "1") (pinfunction "1_1") (pintype "passive"))
      (node (ref "C85") (pin "1") (pinfunction "1_1") (pintype "passive"))
      (node (ref "C96") (pin "1") (pinfunction "1_1") (pintype "passive"))
      (node (ref "CN15") (pin "3") (pinfunction "3_3") (pintype "passive"))
      (node (ref "CN15") (pin "5") (pinfunction "5_5") (pintype "passive"))
      (node (ref "CN15") (pin "6") (pinfunction "6_6") (pintype "passive"))
      (node (ref "CN16") (pin "3") (pinfunction "3_3") (pintype "passive"))
      (node (ref "CN16") (pin "5") (pinfunction "5_5") (pintype "passive"))
      (node (ref "CN16") (pin "6") (pinfunction "6_6") (pintype "passive"))
      (node (ref "CN17") (pin "3") (pinfunction "3_3") (pintype "passive"))
      (node (ref "CN17") (pin "5") (pinfunction "5_5") (pintype "passive"))
      (node (ref "CN17") (pin "6") (pinfunction "6_6") (pintype "passive"))
      (node (ref "CN5") (pin "3") (pinfunction "3_3") (pintype "passive"))
      (node (ref "CN5") (pin "4") (pinfunction "4_4") (pintype "passive"))
      (node (ref "D10") (pin "2") (pinfunction "A_2") (pintype "passive"))
      (node (ref "D9") (pin "1") (pinfunction "1_1") (pintype "passive"))
      (node (ref "H10") (pin "3") (pinfunction "3_3") (pintype "passive"))
      (node (ref "H4") (pin "1") (pinfunction "1_1") (pintype "passive"))
      (node (ref "H5") (pin "3") (pinfunction "3_3") (pintype "passive"))
      (node (ref "H6") (pin "3") (pinfunction "3_3") (pintype "passive"))
      (node (ref "H7") (pin "3") (pinfunction "3_3") (pintype "passive"))
      (node (ref "H8") (pin "3") (pinfunction "3_3") (pintype "passive"))
      (node (ref "H9") (pin "3") (pinfunction "3_3") (pintype "passive"))
      (node (ref "KEY1") (pin "0") (pinfunction "0_0") (pintype "passive"))
      (node (ref "KEY1") (pin "2") (pinfunction "2_2") (pintype "passive"))
      (node (ref "KEY2") (pin "0") (pinfunction "0_0") (pintype "passive"))
      (node (ref "KEY2") (pin "2") (pinfunction "2_2") (pintype "passive"))
      (node (ref "LED6") (pin "1") (pinfunction "GND_1") (pintype "passive"))
      (node (ref "Q4") (pin "2") (pinfunction "S_2") (pintype "passive"))
      (node (ref "Q5") (pin "2") (pinfunction "S_2") (pintype "passive"))
      (node (ref "Q6") (pin "2") (pinfunction "2_2") (pintype "passive"))
      (node (ref "R10") (pin "1") (pinfunction "1_1") (pintype "passive"))
      (node (ref "R118") (pin "1") (pinfunction "1_1") (pintype "passive"))
      (node (ref "R12") (pin "1") (pinfunction "1_1") (pintype "passive"))
      (node (ref "R137") (pin "1") (pinfunction "1_1") (pintype "passive"))
      (node (ref "R138") (pin "2") (pinfunction "2_2") (pintype "passive"))
      (node (ref "R141") (pin "1") (pinfunction "1_1") (pintype "passive"))
      (node (ref "R142") (pin "1") (pinfunction "1_1") (pintype "passive"))
      (node (ref "R143") (pin "1") (pinfunction "1_1") (pintype "passive"))
      (node (ref "R15") (pin "1") (pinfunction "1_1") (pintype "passive"))
      (node (ref "R18") (pin "1") (pinfunction "1_1") (pintype "passive"))
      (node (ref "R189") (pin "1") (pinfunction "1_1") (pintype "passive"))
      (node (ref "R194") (pin "1") (pinfunction "1_1") (pintype "passive"))
      (node (ref "R197") (pin "1") (pinfunction "1_1") (pintype "passive"))
      (node (ref "SW7") (pin "1") (pinfunction "1_1") (pintype "passive"))
      (node (ref "SW8") (pin "1") (pinfunction "1_1") (pintype "passive"))
      (node (ref "U1") (pin "1") (pinfunction "GND_1") (pintype "passive"))
      (node (ref "U1") (pin "3") (pinfunction "GND_3") (pintype "passive"))
      (node (ref "U10") (pin "4") (pinfunction "GNDA_4") (pintype "passive"))
      (node (ref "U10") (pin "6") (pinfunction "GNDIO_6") (pintype "passive"))
      (node (ref "U10") (pin "7") (pinfunction "PS_7") (pintype "passive"))
      (node (ref "U11") (pin "11") (pinfunction "VSS_11") (pintype "passive"))
      (node (ref "U11") (pin "9") (pinfunction "VSS_9") (pintype "passive"))
      (node (ref "U19") (pin "2") (pinfunction "E_2") (pintype "passive"))
      (node (ref "U2") (pin "4") (pinfunction "PGND_4") (pintype "passive"))
      (node (ref "U2") (pin "8") (pinfunction "SGND_8") (pintype "passive"))
      (node (ref "U2") (pin "9") (pinfunction "GND_9") (pintype "passive"))
      (node (ref "U25") (pin "2") (pinfunction "GND_2") (pintype "passive"))
      (node (ref "U27") (pin "1") (pinfunction "1_1") (pintype "passive"))
      (node (ref "U27") (pin "2") (pinfunction "2_2") (pintype "passive"))
      (node (ref "U27") (pin "3") (pinfunction "3_3") (pintype "passive"))
      (node (ref "U27") (pin "4") (pinfunction "4_4") (pintype "passive"))
      (node (ref "U27") (pin "A1") (pinfunction "GND_A1") (pintype "passive"))
      (node (ref "U27") (pin "A12") (pinfunction "GND_A12") (pintype "passive"))
      (node (ref "U27") (pin "B1") (pinfunction "GND_B1") (pintype "passive"))
      (node (ref "U27") (pin "B12") (pinfunction "GND_B12") (pintype "passive"))
      (node (ref "U29") (pin "1") (pinfunction "GND_1") (pintype "passive"))
      (node (ref "U29") (pin "40") (pinfunction "GND_40") (pintype "passive"))
      (node (ref "U29") (pin "41") (pinfunction "GND_41") (pintype "passive"))
      (node (ref "U30") (pin "1") (pinfunction "S2_1") (pintype "passive"))
      (node (ref "U6") (pin "C2") (pinfunction "VSS_C2") (pintype "passive"))
      (node (ref "U6") (pin "E4") (pinfunction "VSS_E4") (pintype "passive"))
      (node (ref "U6") (pin "E5") (pinfunction "VSS_E5") (pintype "passive"))
      (node (ref "U6") (pin "E6") (pinfunction "VSS_E6") (pintype "passive"))
      (node (ref "U6") (pin "G1") (pinfunction "VSSA_G1") (pintype "passive"))
      (node (ref "U6") (pin "J1") (pinfunction "VSS_J1") (pintype "passive"))
      (node (ref "U7") (pin "2") (pinfunction "GND_2") (pintype "passive"))
      (node (ref "U7") (pin "8") (pinfunction "S_8") (pintype "passive"))
      (node (ref "U8") (pin "2") (pinfunction "GND_2") (pintype "passive"))
      (node (ref "U8") (pin "8") (pinfunction "S_8") (pintype "passive"))
      (node (ref "U9") (pin "2") (pinfunction "GND_2") (pintype "passive"))
      (node (ref "U9") (pin "8") (pinfunction "S_8") (pintype "passive"))
      (node (ref "X10") (pin "3") (pinfunction "3_3") (pintype "passive"))
      (node (ref "X10") (pin "4") (pinfunction "4_4") (pintype "passive"))
      (node (ref "X11") (pin "3") (pinfunction "3_3") (pintype "passive"))
      (node (ref "X11") (pin "4") (pinfunction "4_4") (pintype "passive"))
      (node (ref "X12") (pin "3") (pinfunction "3_3") (pintype "passive"))
      (node (ref "X12") (pin "4") (pinfunction "4_4") (pintype "passive"))
      (node (ref "X13") (pin "2") (pinfunction "GND_2") (pintype "passive"))
      (node (ref "X13") (pin "4") (pinfunction "GND_4") (pintype "passive"))
      (node (ref "X15") (pin "1") (pinfunction "1_1") (pintype "passive"))
      (node (ref "X15") (pin "4") (pinfunction "4_4") (pintype "passive"))
      (node (ref "X15") (pin "5") (pinfunction "5_5") (pintype "passive"))
      (node (ref "X16") (pin "2") (pinfunction "2_2") (pintype "passive"))
      (node (ref "X16") (pin "5") (pinfunction "5_5") (pintype "passive"))
      (node (ref "X16") (pin "6") (pinfunction "6_6") (pintype "passive"))
      (node (ref "X17") (pin "2") (pinfunction "2_2") (pintype "passive"))
      (node (ref "X17") (pin "7") (pinfunction "7_7") (pintype "passive"))
      (node (ref "X17") (pin "8") (pinfunction "8_8") (pintype "passive"))
      (node (ref "X18") (pin "2") (pinfunction "2_2") (pintype "passive"))
      (node (ref "X18") (pin "5") (pinfunction "5_5") (pintype "passive"))
      (node (ref "X18") (pin "6") (pinfunction "6_6") (pintype "passive"))
      (node (ref "X19") (pin "2") (pinfunction "2_2") (pintype "passive"))
      (node (ref "X19") (pin "5") (pinfunction "5_5") (pintype "passive"))
      (node (ref "X19") (pin "6") (pinfunction "6_6") (pintype "passive"))
    )
    (net (code "88") (name "GND_BAT") (class "Default")
      (node (ref "C125") (pin "1") (pinfunction "1_1") (pintype "passive"))
      (node (ref "C126") (pin "1") (pinfunction "1_1") (pintype "passive"))
      (node (ref "C128") (pin "1") (pinfunction "1_1") (pintype "passive"))
      (node (ref "CN11") (pin "1") (pinfunction "1_1") (pintype "passive"))
      (node (ref "D11") (pin "2") (pinfunction "A_2") (pintype "passive"))
      (node (ref "U30") (pin "7") (pinfunction "D2_7") (pintype "passive"))
      (node (ref "U30") (pin "8") (pinfunction "D2_8") (pintype "passive"))
      (node (ref "U30") (pin "9") (pinfunction "D2_9") (pintype "passive"))
      (node (ref "U31") (pin "1") (pinfunction "1_1") (pintype "passive"))
    )
    (net (code "89") (name "Net-(C8-Pad1)") (class "Default")
      (node (ref "C8") (pin "1") (pinfunction "1_1") (pintype "passive"))
      (node (ref "R8") (pin "2") (pinfunction "2_2") (pintype "passive"))
    )
    (net (code "90") (name "Net-(C36-Pad2)") (class "Default")
      (node (ref "C36") (pin "2") (pinfunction "2_2") (pintype "passive"))
      (node (ref "U6") (pin "E7") (pinfunction "VCAP_E7") (pintype "passive"))
    )
    (net (code "91") (name "Net-(C37-Pad1)") (class "Default")
      (node (ref "C37") (pin "1") (pinfunction "1_1") (pintype "passive"))
      (node (ref "U6") (pin "F8") (pinfunction "VCAP_F8") (pintype "passive"))
    )
    (net (code "92") (name "Net-(C128-Pad2)") (class "Default")
      (node (ref "C128") (pin "2") (pinfunction "2_2") (pintype "passive"))
      (node (ref "R190") (pin "1") (pinfunction "1_1") (pintype "passive"))
    )
    (net (code "93") (name "Net-(C130-Pad2)") (class "Default")
      (node (ref "C130") (pin "2") (pinfunction "2_2") (pintype "passive"))
      (node (ref "R196") (pin "1") (pinfunction "1_1") (pintype "passive"))
    )
    (net (code "94") (name "Net-(D8-A)") (class "Default")
      (node (ref "BUZZER3") (pin "2") (pinfunction "2_2") (pintype "passive"))
      (node (ref "D8") (pin "2") (pinfunction "A_2") (pintype "passive"))
      (node (ref "Q6") (pin "3") (pinfunction "3_3") (pintype "passive"))
    )
    (net (code "95") (name "Net-(D11-K)") (class "Default")
      (node (ref "D11") (pin "1") (pinfunction "K_1") (pintype "passive"))
      (node (ref "R192") (pin "1") (pinfunction "1_1") (pintype "passive"))
      (node (ref "R193") (pin "1") (pinfunction "1_1") (pintype "passive"))
    )
    (net (code "96") (name "Net-(H4-Pad3)") (class "Default")
      (node (ref "H4") (pin "3") (pinfunction "3_3") (pintype "passive"))
      (node (ref "R145") (pin "2") (pinfunction "2_2") (pintype "passive"))
    )
    (net (code "97") (name "Net-(LED1-K)") (class "Default")
      (node (ref "LED1") (pin "1") (pinfunction "K_1") (pintype "passive"))
      (node (ref "R197") (pin "2") (pinfunction "2_2") (pintype "passive"))
    )
    (net (code "98") (name "Net-(LED2-K)") (class "Default")
      (node (ref "LED2") (pin "1") (pinfunction "K_1") (pintype "passive"))
      (node (ref "R18") (pin "2") (pinfunction "2_2") (pintype "passive"))
    )
    (net (code "99") (name "Net-(LED3-K)") (class "Default")
      (node (ref "LED3") (pin "1") (pinfunction "K_1") (pintype "passive"))
      (node (ref "R183") (pin "2") (pinfunction "2_2") (pintype "passive"))
    )
    (net (code "100") (name "Net-(LED4--)") (class "Default")
      (node (ref "LED4") (pin "1") (pinfunction "-_1") (pintype "passive"))
      (node (ref "R184") (pin "2") (pinfunction "2_2") (pintype "passive"))
    )
    (net (code "101") (name "Net-(LED5-K)") (class "Default")
      (node (ref "LED5") (pin "1") (pinfunction "K_1") (pintype "passive"))
      (node (ref "R185") (pin "2") (pinfunction "2_2") (pintype "passive"))
    )
    (net (code "102") (name "Net-(LED7---Pad2)") (class "Default")
      (node (ref "LED7") (pin "2") (pinfunction "-_2") (pintype "passive"))
      (node (ref "R187") (pin "1") (pinfunction "1_1") (pintype "passive"))
    )
    (net (code "103") (name "Net-(LED7---Pad4)") (class "Default")
      (node (ref "LED7") (pin "4") (pinfunction "-_4") (pintype "passive"))
      (node (ref "R186") (pin "1") (pinfunction "1_1") (pintype "passive"))
    )
    (net (code "104") (name "Net-(Q4-D)") (class "Default")
      (node (ref "Q4") (pin "3") (pinfunction "D_3") (pintype "passive"))
      (node (ref "R177") (pin "1") (pinfunction "1_1") (pintype "passive"))
      (node (ref "R178") (pin "1") (pinfunction "1_1") (pintype "passive"))
      (node (ref "R179") (pin "1") (pinfunction "1_1") (pintype "passive"))
      (node (ref "R180") (pin "1") (pinfunction "1_1") (pintype "passive"))
    )
    (net (code "105") (name "Net-(Q4-G)") (class "Default")
      (node (ref "Q4") (pin "1") (pinfunction "G_1") (pintype "passive"))
      (node (ref "R141") (pin "2") (pinfunction "2_2") (pintype "passive"))
      (node (ref "R181") (pin "1") (pinfunction "1_1") (pintype "passive"))
    )
    (net (code "106") (name "Net-(Q5-D)") (class "Default")
      (node (ref "CN5") (pin "2") (pinfunction "2_2") (pintype "passive"))
      (node (ref "Q5") (pin "3") (pinfunction "D_3") (pintype "passive"))
    )
    (net (code "107") (name "Net-(Q5-G)") (class "Default")
      (node (ref "Q5") (pin "1") (pinfunction "G_1") (pintype "passive"))
      (node (ref "R142") (pin "2") (pinfunction "2_2") (pintype "passive"))
      (node (ref "R148") (pin "2") (pinfunction "2_2") (pintype "passive"))
    )
    (net (code "108") (name "Net-(Q6-Pad1)") (class "Default")
      (node (ref "Q6") (pin "1") (pinfunction "1_1") (pintype "passive"))
      (node (ref "R143") (pin "2") (pinfunction "2_2") (pintype "passive"))
      (node (ref "R147") (pin "2") (pinfunction "2_2") (pintype "passive"))
    )
    (net (code "109") (name "Net-(Q7-B)") (class "Default")
      (node (ref "C129") (pin "2") (pinfunction "2_2") (pintype "passive"))
      (node (ref "Q7") (pin "1") (pinfunction "B_1") (pintype "passive"))
      (node (ref "R193") (pin "2") (pinfunction "2_2") (pintype "passive"))
    )
    (net (code "110") (name "Net-(Q7-C)") (class "Default")
      (node (ref "C129") (pin "1") (pinfunction "1_1") (pintype "passive"))
      (node (ref "Q7") (pin "3") (pinfunction "C_3") (pintype "passive"))
      (node (ref "R194") (pin "2") (pinfunction "2_2") (pintype "passive"))
      (node (ref "R195") (pin "1") (pinfunction "1_1") (pintype "passive"))
    )
    (net (code "111") (name "Net-(U1-BS)") (class "Default")
      (node (ref "C7") (pin "2") (pinfunction "2_2") (pintype "passive"))
      (node (ref "U1") (pin "7") (pinfunction "BS_7") (pintype "passive"))
    )
    (net (code "112") (name "Net-(U1-EN)") (class "Default")
      (node (ref "R11") (pin "1") (pinfunction "1_1") (pintype "passive"))
      (node (ref "R12") (pin "2") (pinfunction "2_2") (pintype "passive"))
      (node (ref "U1") (pin "12") (pinfunction "EN_12") (pintype "passive"))
    )
    (net (code "113") (name "Net-(U1-VCC)") (class "Default")
      (node (ref "C12") (pin "2") (pinfunction "2_2") (pintype "passive"))
      (node (ref "U1") (pin "8") (pinfunction "VCC_8") (pintype "passive"))
    )
    (net (code "114") (name "Net-(U2-LX)") (class "Default")
      (node (ref "L2") (pin "1") (pinfunction "1_1") (pintype "passive"))
      (node (ref "U2") (pin "6") (pinfunction "LX_6") (pintype "passive"))
    )
    (net (code "115") (name "Net-(U2-PG)") (class "Default")
      (node (ref "R13") (pin "2") (pinfunction "2_2") (pintype "passive"))
      (node (ref "U2") (pin "2") (pinfunction "PG_2") (pintype "passive"))
    )
    (net (code "116") (name "Net-(U11-C1)") (class "Default")
      (node (ref "C85") (pin "2") (pinfunction "2_2") (pintype "passive"))
      (node (ref "U11") (pin "10") (pinfunction "C1_10") (pintype "passive"))
    )
    (net (code "117") (name "Net-(U27-CC1)") (class "Default")
      (node (ref "R137") (pin "2") (pinfunction "2_2") (pintype "passive"))
      (node (ref "U27") (pin "A5") (pinfunction "CC1_A5") (pintype "passive"))
    )
    (net (code "118") (name "Net-(U27-CC2)") (class "Default")
      (node (ref "R138") (pin "1") (pinfunction "1_1") (pintype "passive"))
      (node (ref "U27") (pin "B5") (pinfunction "CC2_B5") (pintype "passive"))
    )
    (net (code "119") (name "unconnected-(CN11-Pad3)") (class "Default")
      (node (ref "CN11") (pin "3") (pinfunction "3_3") (pintype "passive"))
    )
    (net (code "120") (name "unconnected-(CN11-Pad4)") (class "Default")
      (node (ref "CN11") (pin "4") (pinfunction "4_4") (pintype "passive"))
    )
    (net (code "121") (name "unconnected-(LED6-DO-Pad4)") (class "Default")
      (node (ref "LED6") (pin "4") (pinfunction "DO_4") (pintype "passive+no_connect"))
    )
    (net (code "122") (name "unconnected-(U1-ILMT-Pad10)") (class "Default")
      (node (ref "U1") (pin "10") (pinfunction "ILMT_10") (pintype "passive+no_connect"))
    )
    (net (code "123") (name "unconnected-(U2-NC-Pad5)") (class "Default")
      (node (ref "U2") (pin "5") (pinfunction "NC_5") (pintype "passive+no_connect"))
    )
    (net (code "124") (name "unconnected-(U6-PB2-PadG5)") (class "Default")
      (node (ref "U6") (pin "G5") (pinfunction "PB2_G5") (pintype "passive"))
    )
    (net (code "125") (name "unconnected-(U6-PB12-PadK8)") (class "Default")
      (node (ref "U6") (pin "K8") (pinfunction "PB12_K8") (pintype "passive"))
    )
    (net (code "126") (name "unconnected-(U6-PB13-PadJ8)") (class "Default")
      (node (ref "U6") (pin "J8") (pinfunction "PB13_J8") (pintype "passive"))
    )
    (net (code "127") (name "unconnected-(U6-PB14-PadH10)") (class "Default")
      (node (ref "U6") (pin "H10") (pinfunction "PB14_H10") (pintype "passive"))
    )
    (net (code "128") (name "unconnected-(U6-PB15-PadG10)") (class "Default")
      (node (ref "U6") (pin "G10") (pinfunction "PB15_G10") (pintype "passive"))
    )
    (net (code "129") (name "unconnected-(U6-PC0-PadF1)") (class "Default")
      (node (ref "U6") (pin "F1") (pinfunction "PC0_F1") (pintype "passive"))
    )
    (net (code "130") (name "unconnected-(U6-PC1-PadF2)") (class "Default")
      (node (ref "U6") (pin "F2") (pinfunction "PC1_F2") (pintype "passive"))
    )
    (net (code "131") (name "unconnected-(U6-PC2_C-PadE2)") (class "Default")
      (node (ref "U6") (pin "E2") (pinfunction "PC2_C_E2") (pintype "passive"))
    )
    (net (code "132") (name "unconnected-(U6-PC3_C-PadF3)") (class "Default")
      (node (ref "U6") (pin "F3") (pinfunction "PC3_C_F3") (pintype "passive"))
    )
    (net (code "133") (name "unconnected-(U6-PC8-PadF9)") (class "Default")
      (node (ref "U6") (pin "F9") (pinfunction "PC8_F9") (pintype "passive"))
    )
    (net (code "134") (name "unconnected-(U6-PC10-PadB9)") (class "Default")
      (node (ref "U6") (pin "B9") (pinfunction "PC10_B9") (pintype "passive"))
    )
    (net (code "135") (name "unconnected-(U6-PD1-PadE8)") (class "Default")
      (node (ref "U6") (pin "E8") (pinfunction "PD1_E8") (pintype "passive"))
    )
    (net (code "136") (name "unconnected-(U6-PD3-PadC7)") (class "Default")
      (node (ref "U6") (pin "C7") (pinfunction "PD3_C7") (pintype "passive"))
    )
    (net (code "137") (name "unconnected-(U6-PD4-PadD7)") (class "Default")
      (node (ref "U6") (pin "D7") (pinfunction "PD4_D7") (pintype "passive"))
    )
    (net (code "138") (name "unconnected-(U6-PD8-PadK9)") (class "Default")
      (node (ref "U6") (pin "K9") (pinfunction "PD8_K9") (pintype "passive"))
    )
    (net (code "139") (name "unconnected-(U6-PD9-PadJ9)") (class "Default")
      (node (ref "U6") (pin "J9") (pinfunction "PD9_J9") (pintype "passive"))
    )
    (net (code "140") (name "unconnected-(U6-PD10-PadH9)") (class "Default")
      (node (ref "U6") (pin "H9") (pinfunction "PD10_H9") (pintype "passive"))
    )
    (net (code "141") (name "unconnected-(U6-PD11-PadG9)") (class "Default")
      (node (ref "U6") (pin "G9") (pinfunction "PD11_G9") (pintype "passive"))
    )
    (net (code "142") (name "unconnected-(U6-PDR_ON-PadF7)") (class "Default")
      (node (ref "U6") (pin "F7") (pinfunction "PDR_ON_F7") (pintype "passive"))
    )
    (net (code "143") (name "unconnected-(U6-PE3-PadB3)") (class "Default")
      (node (ref "U6") (pin "B3") (pinfunction "PE3_B3") (pintype "passive"))
    )
    (net (code "144") (name "unconnected-(U6-PE4-PadC3)") (class "Default")
      (node (ref "U6") (pin "C3") (pinfunction "PE4_C3") (pintype "passive"))
    )
    (net (code "145") (name "unconnected-(U6-PE8-PadJ5)") (class "Default")
      (node (ref "U6") (pin "J5") (pinfunction "PE8_J5") (pintype "passive"))
    )
    (net (code "146") (name "unconnected-(U6-PE12-PadJ6)") (class "Default")
      (node (ref "U6") (pin "J6") (pinfunction "PE12_J6") (pintype "passive"))
    )
    (net (code "147") (name "unconnected-(U6-PE13-PadK6)") (class "Default")
      (node (ref "U6") (pin "K6") (pinfunction "PE13_K6") (pintype "passive"))
    )
    (net (code "148") (name "unconnected-(U6-PE15-PadH7)") (class "Default")
      (node (ref "U6") (pin "H7") (pinfunction "PE15_H7") (pintype "passive"))
    )
    (net (code "149") (name "unconnected-(U7-NC-Pad5)") (class "Default")
      (node (ref "U7") (pin "5") (pinfunction "NC_5") (pintype "passive+no_connect"))
    )
    (net (code "150") (name "unconnected-(U8-NC-Pad5)") (class "Default")
      (node (ref "U8") (pin "5") (pinfunction "NC_5") (pintype "passive+no_connect"))
    )
    (net (code "151") (name "unconnected-(U9-NC-Pad5)") (class "Default")
      (node (ref "U9") (pin "5") (pinfunction "NC_5") (pintype "passive+no_connect"))
    )
    (net (code "152") (name "unconnected-(U10-INT2-Pad1)") (class "Default")
      (node (ref "U10") (pin "1") (pinfunction "INT2_1") (pintype "passive+no_connect"))
    )
    (net (code "153") (name "unconnected-(U10-INT4-Pad13)") (class "Default")
      (node (ref "U10") (pin "13") (pinfunction "INT4_13") (pintype "passive+no_connect"))
    )
    (net (code "154") (name "unconnected-(U10-NC-Pad2)") (class "Default")
      (node (ref "U10") (pin "2") (pinfunction "NC_2") (pintype "passive+no_connect"))
    )
    (net (code "155") (name "unconnected-(U11-CAD0-Pad5)") (class "Default")
      (node (ref "U11") (pin "5") (pinfunction "CAD0_5") (pintype "passive+no_connect"))
    )
    (net (code "156") (name "unconnected-(U11-CAD1-Pad6)") (class "Default")
      (node (ref "U11") (pin "6") (pinfunction "CAD1_6") (pintype "passive+no_connect"))
    )
    (net (code "157") (name "unconnected-(U11-NC-Pad3)") (class "Default")
      (node (ref "U11") (pin "3") (pinfunction "NC_3") (pintype "passive+no_connect"))
    )
    (net (code "158") (name "unconnected-(U11-NC-Pad4)") (class "Default")
      (node (ref "U11") (pin "4") (pinfunction "NC_4") (pintype "passive+no_connect"))
    )
    (net (code "159") (name "unconnected-(U11-NC-Pad8)") (class "Default")
      (node (ref "U11") (pin "8") (pinfunction "NC_8") (pintype "passive+no_connect"))
    )
    (net (code "160") (name "unconnected-(U11-NC-Pad12)") (class "Default")
      (node (ref "U11") (pin "12") (pinfunction "NC_12") (pintype "passive+no_connect"))
    )
    (net (code "161") (name "unconnected-(U11-VPP-Pad7)") (class "Default")
      (node (ref "U11") (pin "7") (pinfunction "VPP_7") (pintype "passive+no_connect"))
    )
    (net (code "162") (name "unconnected-(U27-SBU1-PadA8)") (class "Default")
      (node (ref "U27") (pin "A8") (pinfunction "SBU1_A8") (pintype "passive+no_connect"))
    )
    (net (code "163") (name "unconnected-(U27-SBU2-PadB8)") (class "Default")
      (node (ref "U27") (pin "B8") (pinfunction "SBU2_B8") (pintype "passive+no_connect"))
    )
    (net (code "164") (name "unconnected-(U29-IO1-Pad39)") (class "Default")
      (node (ref "U29") (pin "39") (pinfunction "IO1_39") (pintype "passive"))
    )
    (net (code "165") (name "unconnected-(U29-IO2-Pad38)") (class "Default")
      (node (ref "U29") (pin "38") (pinfunction "IO2_38") (pintype "passive"))
    )
    (net (code "166") (name "unconnected-(U29-IO3-Pad15)") (class "Default")
      (node (ref "U29") (pin "15") (pinfunction "IO3_15") (pintype "passive"))
    )
    (net (code "167") (name "unconnected-(U29-IO4-Pad4)") (class "Default")
      (node (ref "U29") (pin "4") (pinfunction "IO4_4") (pintype "passive"))
    )
    (net (code "168") (name "unconnected-(U29-IO5-Pad5)") (class "Default")
      (node (ref "U29") (pin "5") (pinfunction "IO5_5") (pintype "passive"))
    )
    (net (code "169") (name "unconnected-(U29-IO6-Pad6)") (class "Default")
      (node (ref "U29") (pin "6") (pinfunction "IO6_6") (pintype "passive"))
    )
    (net (code "170") (name "unconnected-(U29-IO7-Pad7)") (class "Default")
      (node (ref "U29") (pin "7") (pinfunction "IO7_7") (pintype "passive"))
    )
    (net (code "171") (name "unconnected-(U29-IO8-Pad12)") (class "Default")
      (node (ref "U29") (pin "12") (pinfunction "IO8_12") (pintype "passive"))
    )
    (net (code "172") (name "unconnected-(U29-IO9-Pad17)") (class "Default")
      (node (ref "U29") (pin "17") (pinfunction "IO9_17") (pintype "passive"))
    )
    (net (code "173") (name "unconnected-(U29-IO10-Pad18)") (class "Default")
      (node (ref "U29") (pin "18") (pinfunction "IO10_18") (pintype "passive"))
    )
    (net (code "174") (name "unconnected-(U29-IO11-Pad19)") (class "Default")
      (node (ref "U29") (pin "19") (pinfunction "IO11_19") (pintype "passive"))
    )
    (net (code "175") (name "unconnected-(U29-IO12-Pad20)") (class "Default")
      (node (ref "U29") (pin "20") (pinfunction "IO12_20") (pintype "passive"))
    )
    (net (code "176") (name "unconnected-(U29-IO13-Pad21)") (class "Default")
      (node (ref "U29") (pin "21") (pinfunction "IO13_21") (pintype "passive"))
    )
    (net (code "177") (name "unconnected-(U29-IO14-Pad22)") (class "Default")
      (node (ref "U29") (pin "22") (pinfunction "IO14_22") (pintype "passive"))
    )
    (net (code "178") (name "unconnected-(U29-IO15-Pad8)") (class "Default")
      (node (ref "U29") (pin "8") (pinfunction "IO15_8") (pintype "passive"))
    )
    (net (code "179") (name "unconnected-(U29-IO16-Pad9)") (class "Default")
      (node (ref "U29") (pin "9") (pinfunction "IO16_9") (pintype "passive"))
    )
    (net (code "180") (name "unconnected-(U29-IO17-Pad10)") (class "Default")
      (node (ref "U29") (pin "10") (pinfunction "IO17_10") (pintype "passive"))
    )
    (net (code "181") (name "unconnected-(U29-IO18-Pad11)") (class "Default")
      (node (ref "U29") (pin "11") (pinfunction "IO18_11") (pintype "passive"))
    )
    (net (code "182") (name "unconnected-(U29-IO38-Pad31)") (class "Default")
      (node (ref "U29") (pin "31") (pinfunction "IO38_31") (pintype "passive"))
    )
    (net (code "183") (name "unconnected-(U29-IO39-Pad32)") (class "Default")
      (node (ref "U29") (pin "32") (pinfunction "IO39_32") (pintype "passive"))
    )
    (net (code "184") (name "unconnected-(U29-IO45-Pad26)") (class "Default")
      (node (ref "U29") (pin "26") (pinfunction "IO45_26") (pintype "passive"))
    )
    (net (code "185") (name "unconnected-(U29-IO46-Pad16)") (class "Default")
      (node (ref "U29") (pin "16") (pinfunction "IO46_16") (pintype "passive"))
    )
    (net (code "186") (name "unconnected-(U29-RXD0-Pad36)") (class "Default")
      (node (ref "U29") (pin "36") (pinfunction "RXD0_36") (pintype "passive"))
    )
    (net (code "187") (name "unconnected-(U29-TXD0-Pad37)") (class "Default")
      (node (ref "U29") (pin "37") (pinfunction "TXD0_37") (pintype "passive"))
    )
  )
)
